# posidmux.net
KiCad netlist of a schematic drawn in EAGLE
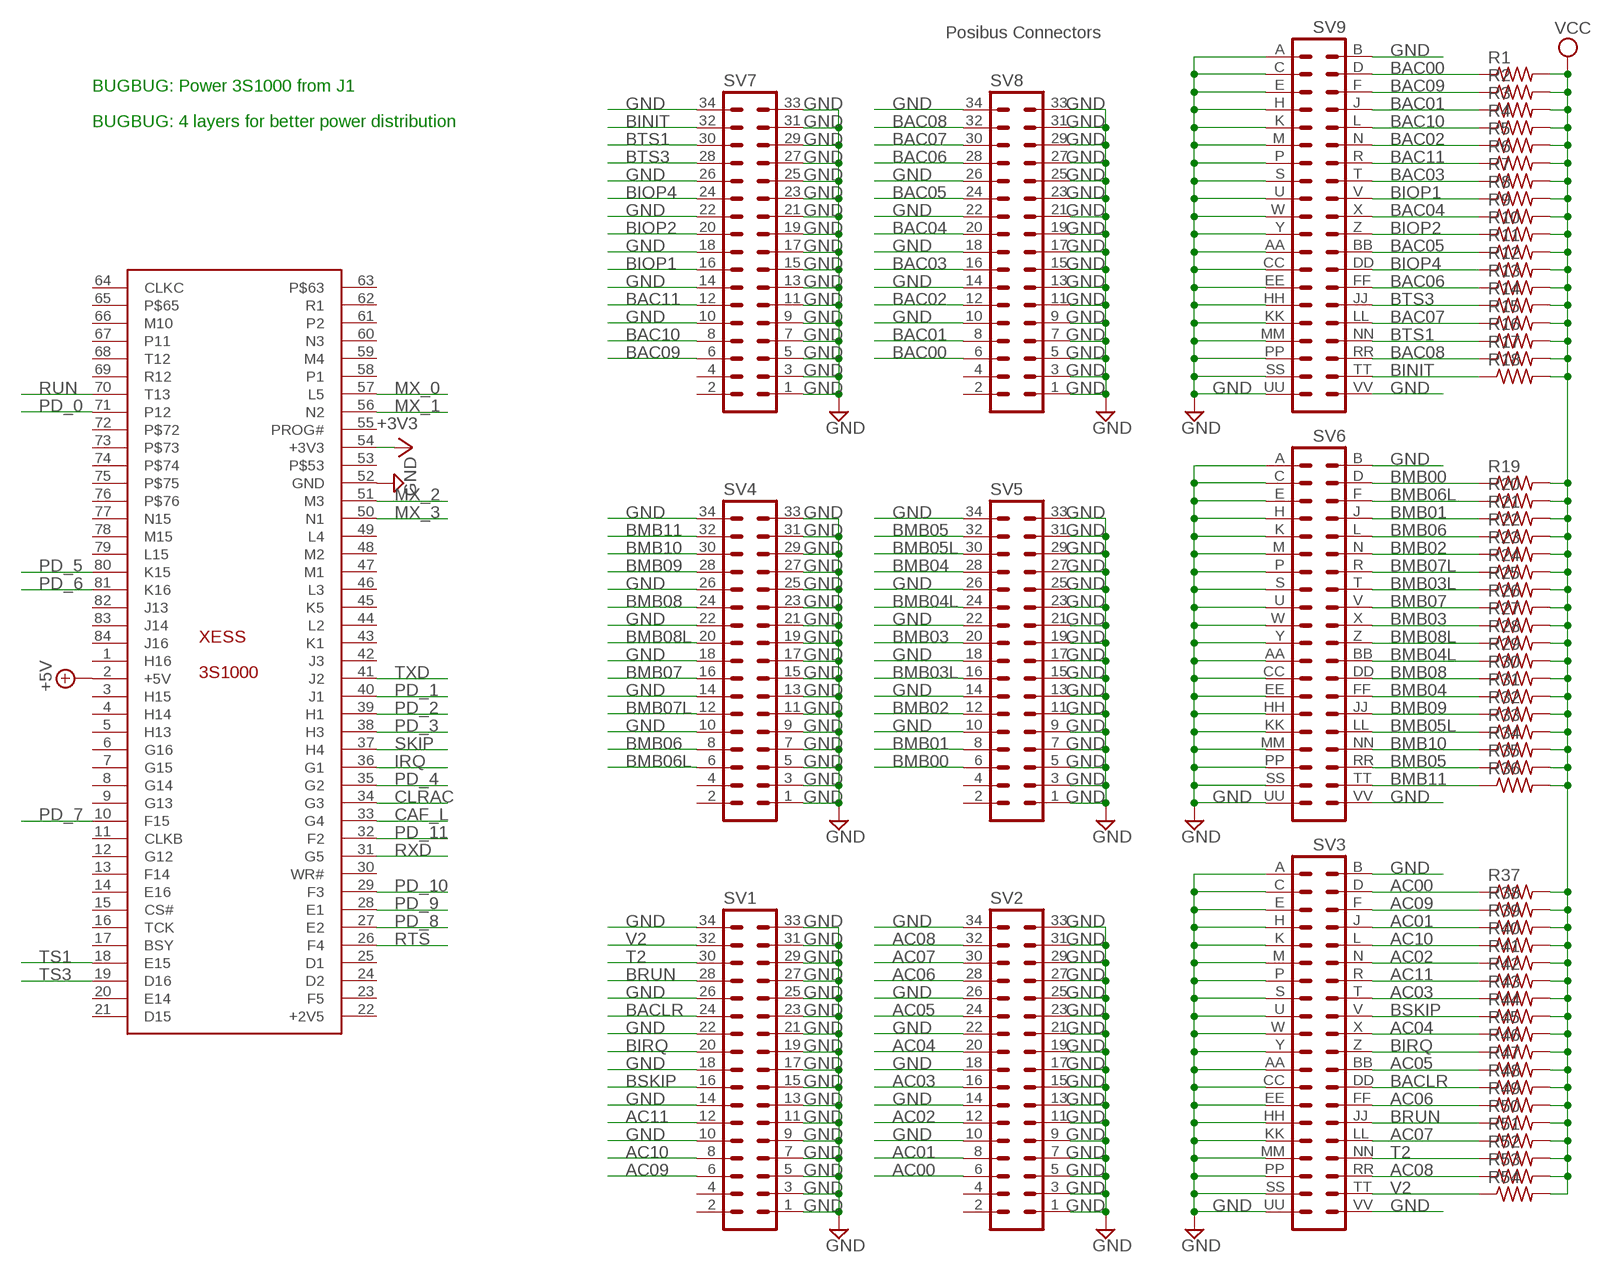
[diagram p0: schematic, sheet 1]
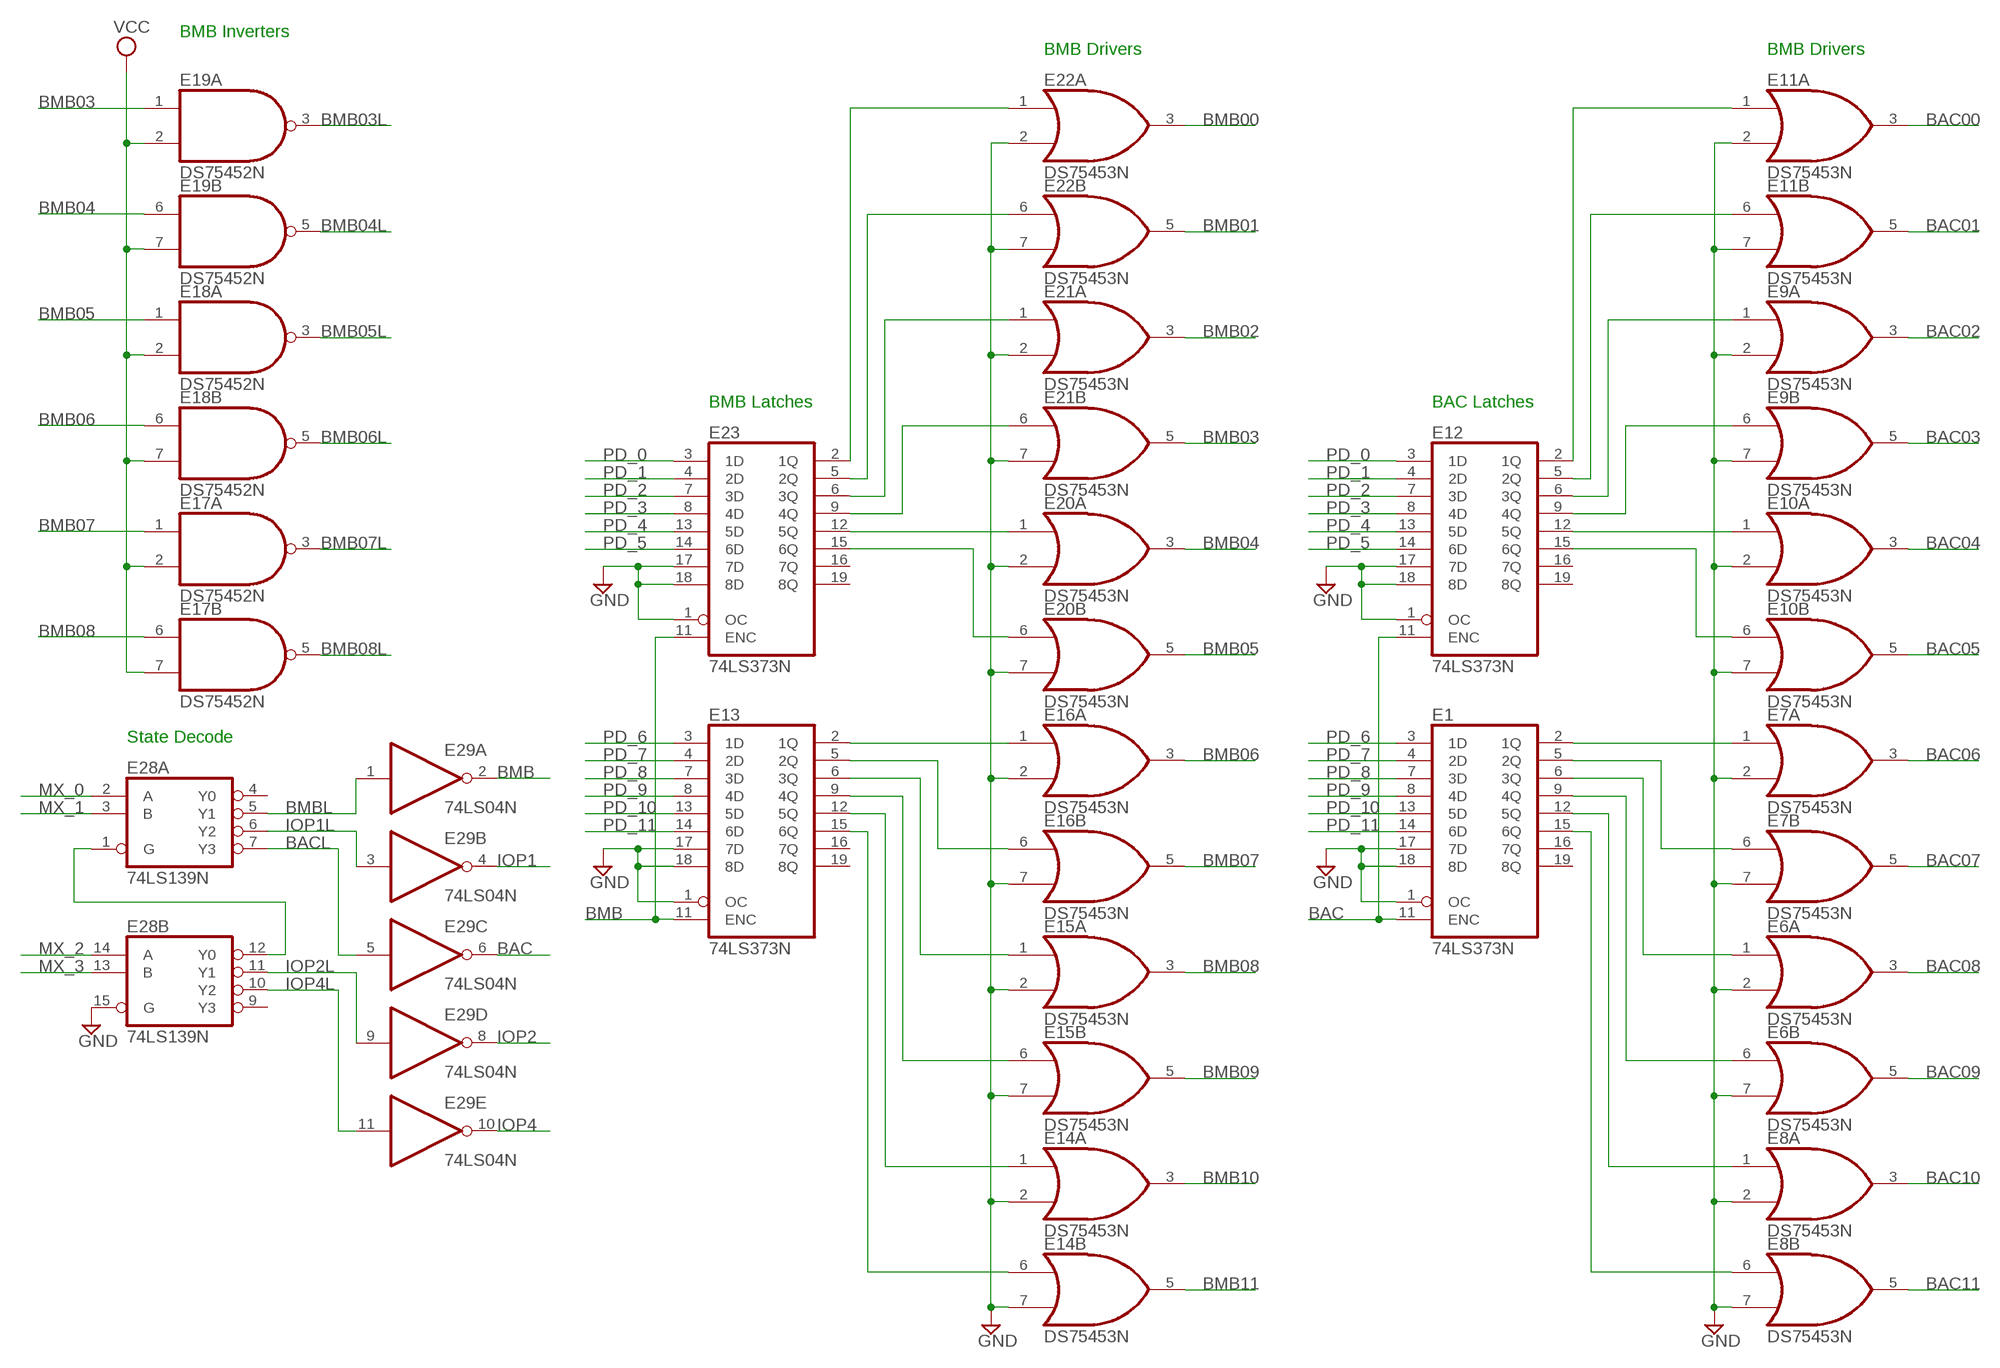
[diagram p1: schematic, sheet 2]
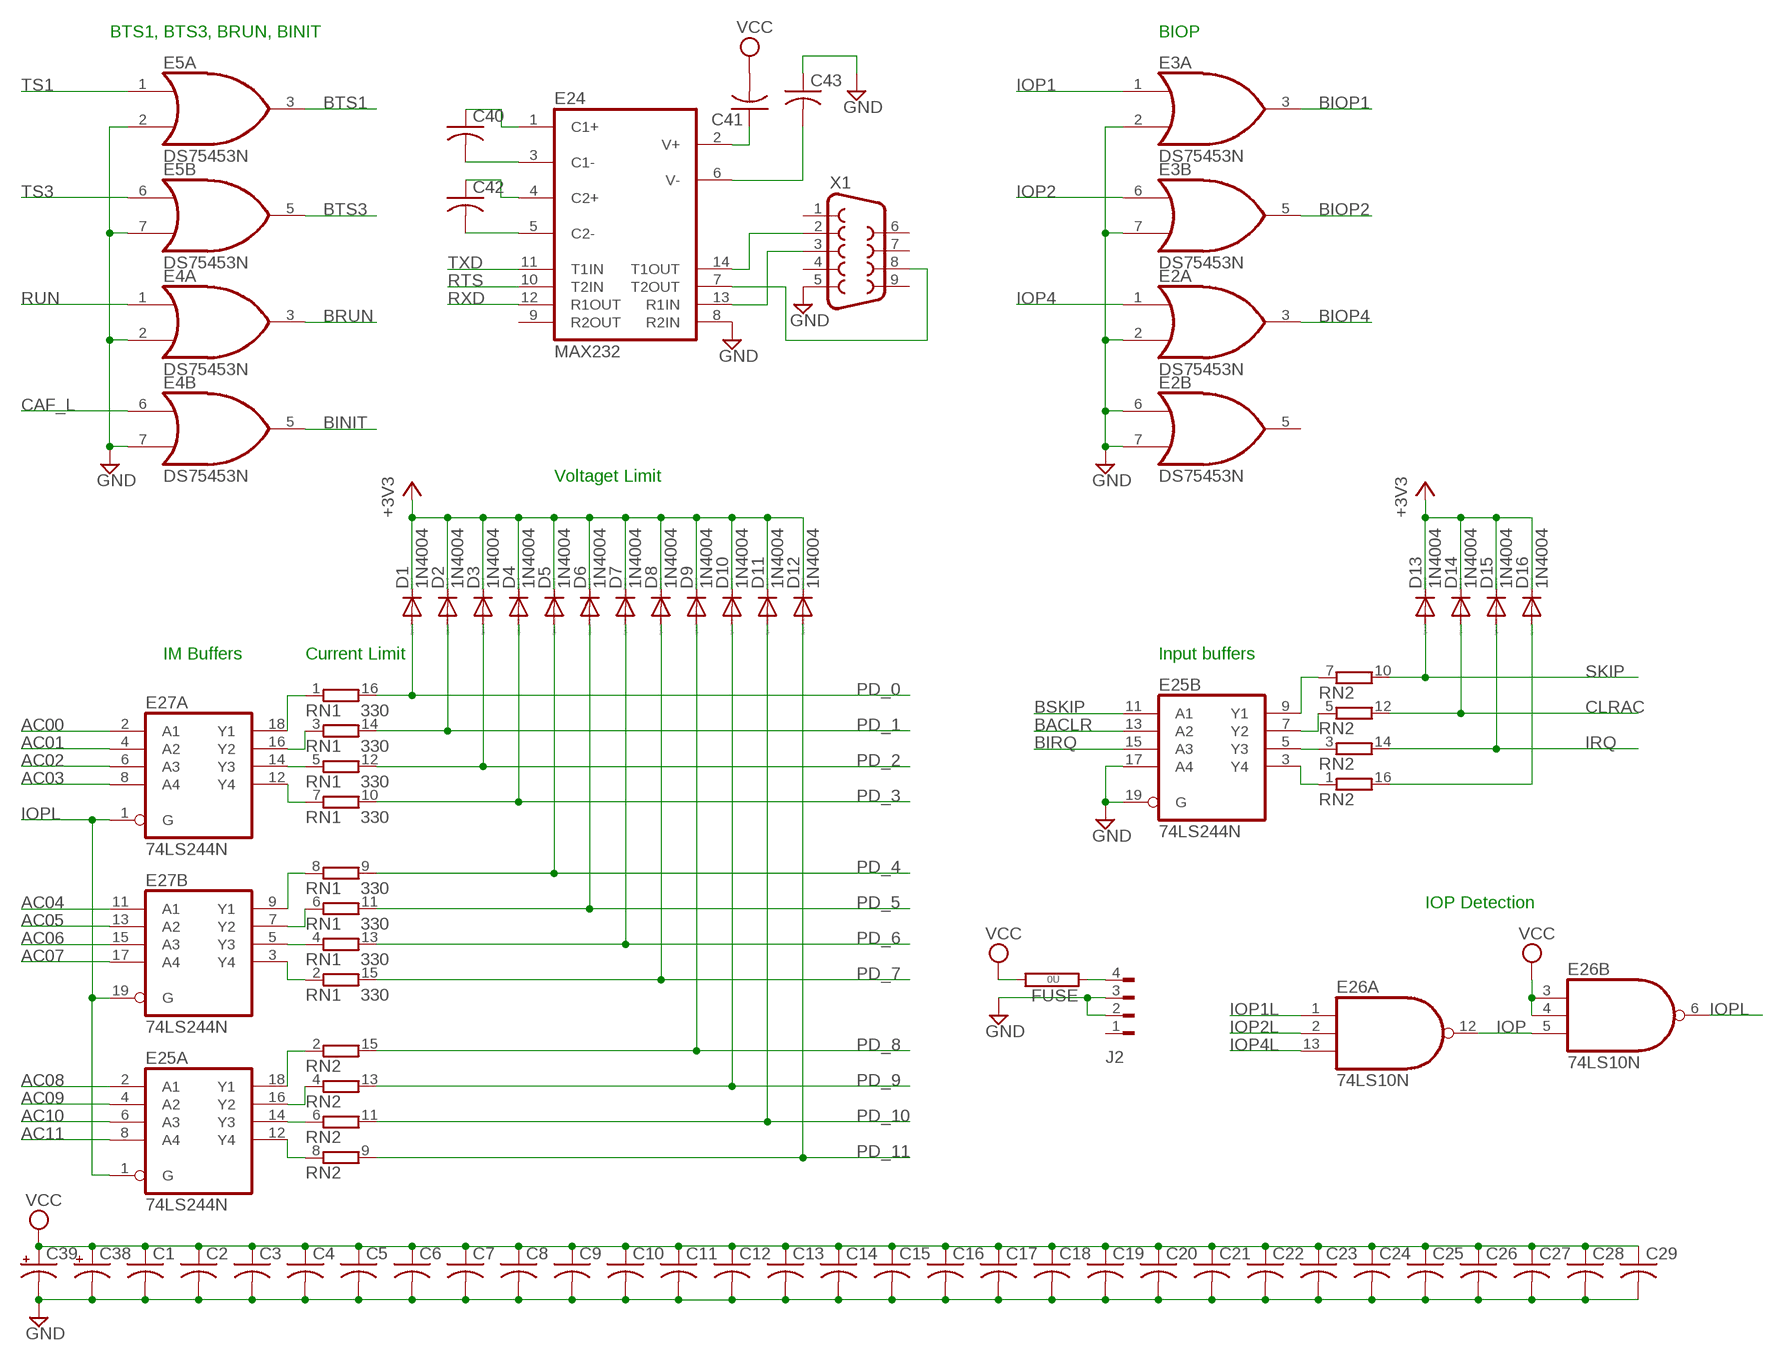
[diagram p2: schematic, sheet 3]

(export (version "E")
  (design (tool "Eeschema 10.0.6"))
  (components
    (comp (ref "E1")
      (value "74LS373N")
      (footprint "eagle-import:DIL20")
      (libsource (lib "eagle-import") (part "74373NLS"))
    )
    (comp (ref "E6")
      (value "DS75453N")
      (footprint "eagle-import:DIL08")
      (libsource (lib "eagle-import") (part "DS75453N"))
    )
    (comp (ref "E7")
      (value "DS75453N")
      (footprint "eagle-import:DIL08")
      (libsource (lib "eagle-import") (part "DS75453N"))
    )
    (comp (ref "E8")
      (value "DS75453N")
      (footprint "eagle-import:DIL08")
      (libsource (lib "eagle-import") (part "DS75453N"))
    )
    (comp (ref "E9")
      (value "DS75453N")
      (footprint "eagle-import:DIL08")
      (libsource (lib "eagle-import") (part "DS75453N"))
    )
    (comp (ref "E10")
      (value "DS75453N")
      (footprint "eagle-import:DIL08")
      (libsource (lib "eagle-import") (part "DS75453N"))
    )
    (comp (ref "E11")
      (value "DS75453N")
      (footprint "eagle-import:DIL08")
      (libsource (lib "eagle-import") (part "DS75453N"))
    )
    (comp (ref "E12")
      (value "74LS373N")
      (footprint "eagle-import:DIL20")
      (libsource (lib "eagle-import") (part "74373NLS"))
    )
    (comp (ref "E13")
      (value "74LS373N")
      (footprint "eagle-import:DIL20")
      (libsource (lib "eagle-import") (part "74373NLS"))
    )
    (comp (ref "E14")
      (value "DS75453N")
      (footprint "eagle-import:DIL08")
      (libsource (lib "eagle-import") (part "DS75453N"))
    )
    (comp (ref "E15")
      (value "DS75453N")
      (footprint "eagle-import:DIL08")
      (libsource (lib "eagle-import") (part "DS75453N"))
    )
    (comp (ref "E16")
      (value "DS75453N")
      (footprint "eagle-import:DIL08")
      (libsource (lib "eagle-import") (part "DS75453N"))
    )
    (comp (ref "E17")
      (value "DS75452N")
      (footprint "eagle-import:DIL08")
      (libsource (lib "eagle-import") (part "DS75452N"))
    )
    (comp (ref "E18")
      (value "DS75452N")
      (footprint "eagle-import:DIL08")
      (libsource (lib "eagle-import") (part "DS75452N"))
    )
    (comp (ref "E19")
      (value "DS75452N")
      (footprint "eagle-import:DIL08")
      (libsource (lib "eagle-import") (part "DS75452N"))
    )
    (comp (ref "E20")
      (value "DS75453N")
      (footprint "eagle-import:DIL08")
      (libsource (lib "eagle-import") (part "DS75453N"))
    )
    (comp (ref "E21")
      (value "DS75453N")
      (footprint "eagle-import:DIL08")
      (libsource (lib "eagle-import") (part "DS75453N"))
    )
    (comp (ref "E22")
      (value "DS75453N")
      (footprint "eagle-import:DIL08")
      (libsource (lib "eagle-import") (part "DS75453N"))
    )
    (comp (ref "E23")
      (value "74LS373N")
      (footprint "eagle-import:DIL20")
      (libsource (lib "eagle-import") (part "74373NLS"))
    )
    (comp (ref "E28")
      (value "74LS139N")
      (footprint "eagle-import:DIL16")
      (libsource (lib "eagle-import") (part "74139NLS"))
    )
    (comp (ref "E29")
      (value "74LS04N")
      (footprint "eagle-import:DIL14")
      (libsource (lib "eagle-import") (part "7404NLS"))
    )
    (comp (ref "C1")
      (value "C-US050-025X075")
      (footprint "eagle-import:C050-025X075")
      (libsource (lib "eagle-import") (part "C-US050-025X075"))
    )
    (comp (ref "C2")
      (value "C-US050-025X075")
      (footprint "eagle-import:C050-025X075")
      (libsource (lib "eagle-import") (part "C-US050-025X075"))
    )
    (comp (ref "C3")
      (value "C-US050-025X075")
      (footprint "eagle-import:C050-025X075")
      (libsource (lib "eagle-import") (part "C-US050-025X075"))
    )
    (comp (ref "C4")
      (value "C-US050-025X075")
      (footprint "eagle-import:C050-025X075")
      (libsource (lib "eagle-import") (part "C-US050-025X075"))
    )
    (comp (ref "C5")
      (value "C-US050-025X075")
      (footprint "eagle-import:C050-025X075")
      (libsource (lib "eagle-import") (part "C-US050-025X075"))
    )
    (comp (ref "C6")
      (value "C-US050-025X075")
      (footprint "eagle-import:C050-025X075")
      (libsource (lib "eagle-import") (part "C-US050-025X075"))
    )
    (comp (ref "C7")
      (value "C-US050-025X075")
      (footprint "eagle-import:C050-025X075")
      (libsource (lib "eagle-import") (part "C-US050-025X075"))
    )
    (comp (ref "C8")
      (value "C-US050-025X075")
      (footprint "eagle-import:C050-025X075")
      (libsource (lib "eagle-import") (part "C-US050-025X075"))
    )
    (comp (ref "C9")
      (value "C-US050-025X075")
      (footprint "eagle-import:C050-025X075")
      (libsource (lib "eagle-import") (part "C-US050-025X075"))
    )
    (comp (ref "C10")
      (value "C-US050-025X075")
      (footprint "eagle-import:C050-025X075")
      (libsource (lib "eagle-import") (part "C-US050-025X075"))
    )
    (comp (ref "C11")
      (value "C-US050-025X075")
      (footprint "eagle-import:C050-025X075")
      (libsource (lib "eagle-import") (part "C-US050-025X075"))
    )
    (comp (ref "C12")
      (value "C-US050-025X075")
      (footprint "eagle-import:C050-025X075")
      (libsource (lib "eagle-import") (part "C-US050-025X075"))
    )
    (comp (ref "C13")
      (value "C-US050-025X075")
      (footprint "eagle-import:C050-025X075")
      (libsource (lib "eagle-import") (part "C-US050-025X075"))
    )
    (comp (ref "C14")
      (value "C-US050-025X075")
      (footprint "eagle-import:C050-025X075")
      (libsource (lib "eagle-import") (part "C-US050-025X075"))
    )
    (comp (ref "C15")
      (value "C-US050-025X075")
      (footprint "eagle-import:C050-025X075")
      (libsource (lib "eagle-import") (part "C-US050-025X075"))
    )
    (comp (ref "C16")
      (value "C-US050-025X075")
      (footprint "eagle-import:C050-025X075")
      (libsource (lib "eagle-import") (part "C-US050-025X075"))
    )
    (comp (ref "C17")
      (value "C-US050-025X075")
      (footprint "eagle-import:C050-025X075")
      (libsource (lib "eagle-import") (part "C-US050-025X075"))
    )
    (comp (ref "C18")
      (value "C-US050-025X075")
      (footprint "eagle-import:C050-025X075")
      (libsource (lib "eagle-import") (part "C-US050-025X075"))
    )
    (comp (ref "C19")
      (value "C-US050-025X075")
      (footprint "eagle-import:C050-025X075")
      (libsource (lib "eagle-import") (part "C-US050-025X075"))
    )
    (comp (ref "C20")
      (value "C-US050-025X075")
      (footprint "eagle-import:C050-025X075")
      (libsource (lib "eagle-import") (part "C-US050-025X075"))
    )
    (comp (ref "C21")
      (value "C-US050-025X075")
      (footprint "eagle-import:C050-025X075")
      (libsource (lib "eagle-import") (part "C-US050-025X075"))
    )
    (comp (ref "C22")
      (value "C-US050-025X075")
      (footprint "eagle-import:C050-025X075")
      (libsource (lib "eagle-import") (part "C-US050-025X075"))
    )
    (comp (ref "C23")
      (value "C-US050-025X075")
      (footprint "eagle-import:C050-025X075")
      (libsource (lib "eagle-import") (part "C-US050-025X075"))
    )
    (comp (ref "C24")
      (value "C-US050-025X075")
      (footprint "eagle-import:C050-025X075")
      (libsource (lib "eagle-import") (part "C-US050-025X075"))
    )
    (comp (ref "C25")
      (value "C-US050-025X075")
      (footprint "eagle-import:C050-025X075")
      (libsource (lib "eagle-import") (part "C-US050-025X075"))
    )
    (comp (ref "C26")
      (value "C-US050-025X075")
      (footprint "eagle-import:C050-025X075")
      (libsource (lib "eagle-import") (part "C-US050-025X075"))
    )
    (comp (ref "C27")
      (value "C-US050-025X075")
      (footprint "eagle-import:C050-025X075")
      (libsource (lib "eagle-import") (part "C-US050-025X075"))
    )
    (comp (ref "C28")
      (value "C-US050-025X075")
      (footprint "eagle-import:C050-025X075")
      (libsource (lib "eagle-import") (part "C-US050-025X075"))
    )
    (comp (ref "C29")
      (value "C-US050-025X075")
      (footprint "eagle-import:C050-025X075")
      (libsource (lib "eagle-import") (part "C-US050-025X075"))
    )
    (comp (ref "C38")
      (value "CPOL-USE22-6AXIAL")
      (footprint "eagle-import:E22-6")
      (libsource (lib "eagle-import") (part "CPOL-USE22-6AXIAL"))
    )
    (comp (ref "C39")
      (value "CPOL-USE22-6AXIAL")
      (footprint "eagle-import:E22-6")
      (libsource (lib "eagle-import") (part "CPOL-USE22-6AXIAL"))
    )
    (comp (ref "C40")
      (value "C-US050-025X075")
      (footprint "eagle-import:C050-025X075")
      (libsource (lib "eagle-import") (part "C-US050-025X075"))
    )
    (comp (ref "C41")
      (value "C-US050-025X075")
      (footprint "eagle-import:C050-025X075")
      (libsource (lib "eagle-import") (part "C-US050-025X075"))
    )
    (comp (ref "C42")
      (value "C-US050-025X075")
      (footprint "eagle-import:C050-025X075")
      (libsource (lib "eagle-import") (part "C-US050-025X075"))
    )
    (comp (ref "C43")
      (value "C-US050-025X075")
      (footprint "eagle-import:C050-025X075")
      (libsource (lib "eagle-import") (part "C-US050-025X075"))
    )
    (comp (ref "D1")
      (value "1N4004")
      (footprint "eagle-import:DO41-10")
      (libsource (lib "eagle-import") (part "1N4004"))
    )
    (comp (ref "D2")
      (value "1N4004")
      (footprint "eagle-import:DO41-10")
      (libsource (lib "eagle-import") (part "1N4004"))
    )
    (comp (ref "D3")
      (value "1N4004")
      (footprint "eagle-import:DO41-10")
      (libsource (lib "eagle-import") (part "1N4004"))
    )
    (comp (ref "D4")
      (value "1N4004")
      (footprint "eagle-import:DO41-10")
      (libsource (lib "eagle-import") (part "1N4004"))
    )
    (comp (ref "D5")
      (value "1N4004")
      (footprint "eagle-import:DO41-10")
      (libsource (lib "eagle-import") (part "1N4004"))
    )
    (comp (ref "D6")
      (value "1N4004")
      (footprint "eagle-import:DO41-10")
      (libsource (lib "eagle-import") (part "1N4004"))
    )
    (comp (ref "D7")
      (value "1N4004")
      (footprint "eagle-import:DO41-10")
      (libsource (lib "eagle-import") (part "1N4004"))
    )
    (comp (ref "D8")
      (value "1N4004")
      (footprint "eagle-import:DO41-10")
      (libsource (lib "eagle-import") (part "1N4004"))
    )
    (comp (ref "D9")
      (value "1N4004")
      (footprint "eagle-import:DO41-10")
      (libsource (lib "eagle-import") (part "1N4004"))
    )
    (comp (ref "D10")
      (value "1N4004")
      (footprint "eagle-import:DO41-10")
      (libsource (lib "eagle-import") (part "1N4004"))
    )
    (comp (ref "D11")
      (value "1N4004")
      (footprint "eagle-import:DO41-10")
      (libsource (lib "eagle-import") (part "1N4004"))
    )
    (comp (ref "D12")
      (value "1N4004")
      (footprint "eagle-import:DO41-10")
      (libsource (lib "eagle-import") (part "1N4004"))
    )
    (comp (ref "D13")
      (value "1N4004")
      (footprint "eagle-import:DO41-10")
      (libsource (lib "eagle-import") (part "1N4004"))
    )
    (comp (ref "D14")
      (value "1N4004")
      (footprint "eagle-import:DO41-10")
      (libsource (lib "eagle-import") (part "1N4004"))
    )
    (comp (ref "D15")
      (value "1N4004")
      (footprint "eagle-import:DO41-10")
      (libsource (lib "eagle-import") (part "1N4004"))
    )
    (comp (ref "D16")
      (value "1N4004")
      (footprint "eagle-import:DO41-10")
      (libsource (lib "eagle-import") (part "1N4004"))
    )
    (comp (ref "E2")
      (value "DS75453N")
      (footprint "eagle-import:DIL08")
      (libsource (lib "eagle-import") (part "DS75453N"))
    )
    (comp (ref "E3")
      (value "DS75453N")
      (footprint "eagle-import:DIL08")
      (libsource (lib "eagle-import") (part "DS75453N"))
    )
    (comp (ref "E4")
      (value "DS75453N")
      (footprint "eagle-import:DIL08")
      (libsource (lib "eagle-import") (part "DS75453N"))
    )
    (comp (ref "E5")
      (value "DS75453N")
      (footprint "eagle-import:DIL08")
      (libsource (lib "eagle-import") (part "DS75453N"))
    )
    (comp (ref "E24")
      (value "MAX232")
      (footprint "eagle-import:DIL16")
      (fields (field (name "MF") "MAXIM") (field (name "MPN") "MAX232ACPE+"))
      (libsource (lib "eagle-import") (part "MAX232"))
    )
    (comp (ref "E25")
      (value "74LS244N")
      (footprint "eagle-import:DIL20")
      (libsource (lib "eagle-import") (part "74244NLS"))
    )
    (comp (ref "E26")
      (value "74LS10N")
      (footprint "eagle-import:DIL14")
      (libsource (lib "eagle-import") (part "7410NLS"))
    )
    (comp (ref "E27")
      (value "74LS244N")
      (footprint "eagle-import:DIL20")
      (libsource (lib "eagle-import") (part "74244NLS"))
    )
    (comp (ref "FUSE")
      (value "0R")
      (footprint "eagle-import:0R_10")
      (libsource (lib "eagle-import") (part "0R"))
    )
    (comp (ref "J2")
      (value "FLOPPY-4")
      (footprint "eagle-import:FLOPPY-4")
      (libsource (lib "eagle-import") (part "FLOPPY-4"))
    )
    (comp (ref "RN1")
      (value "330")
      (footprint "eagle-import:DIL16")
      (libsource (lib "eagle-import") (part "8R-P"))
    )
    (comp (ref "RN2")
      (value "8R-P")
      (footprint "eagle-import:DIL16")
      (libsource (lib "eagle-import") (part "8R-P"))
    )
    (comp (ref "X1")
      (value "F09HP")
      (footprint "eagle-import:F09HP")
      (libsource (lib "eagle-import") (part "F09HP"))
    )
    (comp (ref "R1")
      (value "R-US_0207/10")
      (footprint "eagle-import:0207_10")
      (libsource (lib "eagle-import") (part "R-US_0207/10"))
    )
    (comp (ref "R2")
      (value "R-US_0207/10")
      (footprint "eagle-import:0207_10")
      (libsource (lib "eagle-import") (part "R-US_0207/10"))
    )
    (comp (ref "R3")
      (value "R-US_0207/10")
      (footprint "eagle-import:0207_10")
      (libsource (lib "eagle-import") (part "R-US_0207/10"))
    )
    (comp (ref "R4")
      (value "R-US_0207/10")
      (footprint "eagle-import:0207_10")
      (libsource (lib "eagle-import") (part "R-US_0207/10"))
    )
    (comp (ref "R5")
      (value "R-US_0207/10")
      (footprint "eagle-import:0207_10")
      (libsource (lib "eagle-import") (part "R-US_0207/10"))
    )
    (comp (ref "R6")
      (value "R-US_0207/10")
      (footprint "eagle-import:0207_10")
      (libsource (lib "eagle-import") (part "R-US_0207/10"))
    )
    (comp (ref "R7")
      (value "R-US_0207/10")
      (footprint "eagle-import:0207_10")
      (libsource (lib "eagle-import") (part "R-US_0207/10"))
    )
    (comp (ref "R8")
      (value "R-US_0207/10")
      (footprint "eagle-import:0207_10")
      (libsource (lib "eagle-import") (part "R-US_0207/10"))
    )
    (comp (ref "R9")
      (value "R-US_0207/10")
      (footprint "eagle-import:0207_10")
      (libsource (lib "eagle-import") (part "R-US_0207/10"))
    )
    (comp (ref "R10")
      (value "R-US_0207/10")
      (footprint "eagle-import:0207_10")
      (libsource (lib "eagle-import") (part "R-US_0207/10"))
    )
    (comp (ref "R11")
      (value "R-US_0207/10")
      (footprint "eagle-import:0207_10")
      (libsource (lib "eagle-import") (part "R-US_0207/10"))
    )
    (comp (ref "R12")
      (value "R-US_0207/10")
      (footprint "eagle-import:0207_10")
      (libsource (lib "eagle-import") (part "R-US_0207/10"))
    )
    (comp (ref "R13")
      (value "R-US_0207/10")
      (footprint "eagle-import:0207_10")
      (libsource (lib "eagle-import") (part "R-US_0207/10"))
    )
    (comp (ref "R14")
      (value "R-US_0207/10")
      (footprint "eagle-import:0207_10")
      (libsource (lib "eagle-import") (part "R-US_0207/10"))
    )
    (comp (ref "R15")
      (value "R-US_0207/10")
      (footprint "eagle-import:0207_10")
      (libsource (lib "eagle-import") (part "R-US_0207/10"))
    )
    (comp (ref "R16")
      (value "R-US_0207/10")
      (footprint "eagle-import:0207_10")
      (libsource (lib "eagle-import") (part "R-US_0207/10"))
    )
    (comp (ref "R17")
      (value "R-US_0207/10")
      (footprint "eagle-import:0207_10")
      (libsource (lib "eagle-import") (part "R-US_0207/10"))
    )
    (comp (ref "R18")
      (value "R-US_0207/10")
      (footprint "eagle-import:0207_10")
      (libsource (lib "eagle-import") (part "R-US_0207/10"))
    )
    (comp (ref "R19")
      (value "R-US_0207/10")
      (footprint "eagle-import:0207_10")
      (libsource (lib "eagle-import") (part "R-US_0207/10"))
    )
    (comp (ref "R20")
      (value "R-US_0207/10")
      (footprint "eagle-import:0207_10")
      (libsource (lib "eagle-import") (part "R-US_0207/10"))
    )
    (comp (ref "R21")
      (value "R-US_0207/10")
      (footprint "eagle-import:0207_10")
      (libsource (lib "eagle-import") (part "R-US_0207/10"))
    )
    (comp (ref "R22")
      (value "R-US_0207/10")
      (footprint "eagle-import:0207_10")
      (libsource (lib "eagle-import") (part "R-US_0207/10"))
    )
    (comp (ref "R23")
      (value "R-US_0207/10")
      (footprint "eagle-import:0207_10")
      (libsource (lib "eagle-import") (part "R-US_0207/10"))
    )
    (comp (ref "R24")
      (value "R-US_0207/10")
      (footprint "eagle-import:0207_10")
      (libsource (lib "eagle-import") (part "R-US_0207/10"))
    )
    (comp (ref "R25")
      (value "R-US_0207/10")
      (footprint "eagle-import:0207_10")
      (libsource (lib "eagle-import") (part "R-US_0207/10"))
    )
    (comp (ref "R26")
      (value "R-US_0207/10")
      (footprint "eagle-import:0207_10")
      (libsource (lib "eagle-import") (part "R-US_0207/10"))
    )
    (comp (ref "R27")
      (value "R-US_0207/10")
      (footprint "eagle-import:0207_10")
      (libsource (lib "eagle-import") (part "R-US_0207/10"))
    )
    (comp (ref "R28")
      (value "R-US_0207/10")
      (footprint "eagle-import:0207_10")
      (libsource (lib "eagle-import") (part "R-US_0207/10"))
    )
    (comp (ref "R29")
      (value "R-US_0207/10")
      (footprint "eagle-import:0207_10")
      (libsource (lib "eagle-import") (part "R-US_0207/10"))
    )
    (comp (ref "R30")
      (value "R-US_0207/10")
      (footprint "eagle-import:0207_10")
      (libsource (lib "eagle-import") (part "R-US_0207/10"))
    )
    (comp (ref "R31")
      (value "R-US_0207/10")
      (footprint "eagle-import:0207_10")
      (libsource (lib "eagle-import") (part "R-US_0207/10"))
    )
    (comp (ref "R32")
      (value "R-US_0207/10")
      (footprint "eagle-import:0207_10")
      (libsource (lib "eagle-import") (part "R-US_0207/10"))
    )
    (comp (ref "R33")
      (value "R-US_0207/10")
      (footprint "eagle-import:0207_10")
      (libsource (lib "eagle-import") (part "R-US_0207/10"))
    )
    (comp (ref "R34")
      (value "R-US_0207/10")
      (footprint "eagle-import:0207_10")
      (libsource (lib "eagle-import") (part "R-US_0207/10"))
    )
    (comp (ref "R35")
      (value "R-US_0207/10")
      (footprint "eagle-import:0207_10")
      (libsource (lib "eagle-import") (part "R-US_0207/10"))
    )
    (comp (ref "R36")
      (value "R-US_0207/10")
      (footprint "eagle-import:0207_10")
      (libsource (lib "eagle-import") (part "R-US_0207/10"))
    )
    (comp (ref "R37")
      (value "R-US_0207/10")
      (footprint "eagle-import:0207_10")
      (libsource (lib "eagle-import") (part "R-US_0207/10"))
    )
    (comp (ref "R38")
      (value "R-US_0207/10")
      (footprint "eagle-import:0207_10")
      (libsource (lib "eagle-import") (part "R-US_0207/10"))
    )
    (comp (ref "R39")
      (value "R-US_0207/10")
      (footprint "eagle-import:0207_10")
      (libsource (lib "eagle-import") (part "R-US_0207/10"))
    )
    (comp (ref "R40")
      (value "R-US_0207/10")
      (footprint "eagle-import:0207_10")
      (libsource (lib "eagle-import") (part "R-US_0207/10"))
    )
    (comp (ref "R41")
      (value "R-US_0207/10")
      (footprint "eagle-import:0207_10")
      (libsource (lib "eagle-import") (part "R-US_0207/10"))
    )
    (comp (ref "R42")
      (value "R-US_0207/10")
      (footprint "eagle-import:0207_10")
      (libsource (lib "eagle-import") (part "R-US_0207/10"))
    )
    (comp (ref "R43")
      (value "R-US_0207/10")
      (footprint "eagle-import:0207_10")
      (libsource (lib "eagle-import") (part "R-US_0207/10"))
    )
    (comp (ref "R44")
      (value "R-US_0207/10")
      (footprint "eagle-import:0207_10")
      (libsource (lib "eagle-import") (part "R-US_0207/10"))
    )
    (comp (ref "R45")
      (value "R-US_0207/10")
      (footprint "eagle-import:0207_10")
      (libsource (lib "eagle-import") (part "R-US_0207/10"))
    )
    (comp (ref "R46")
      (value "R-US_0207/10")
      (footprint "eagle-import:0207_10")
      (libsource (lib "eagle-import") (part "R-US_0207/10"))
    )
    (comp (ref "R47")
      (value "R-US_0207/10")
      (footprint "eagle-import:0207_10")
      (libsource (lib "eagle-import") (part "R-US_0207/10"))
    )
    (comp (ref "R48")
      (value "R-US_0207/10")
      (footprint "eagle-import:0207_10")
      (libsource (lib "eagle-import") (part "R-US_0207/10"))
    )
    (comp (ref "R49")
      (value "R-US_0207/10")
      (footprint "eagle-import:0207_10")
      (libsource (lib "eagle-import") (part "R-US_0207/10"))
    )
    (comp (ref "R50")
      (value "R-US_0207/10")
      (footprint "eagle-import:0207_10")
      (libsource (lib "eagle-import") (part "R-US_0207/10"))
    )
    (comp (ref "R51")
      (value "R-US_0207/10")
      (footprint "eagle-import:0207_10")
      (libsource (lib "eagle-import") (part "R-US_0207/10"))
    )
    (comp (ref "R52")
      (value "R-US_0207/10")
      (footprint "eagle-import:0207_10")
      (libsource (lib "eagle-import") (part "R-US_0207/10"))
    )
    (comp (ref "R53")
      (value "R-US_0207/10")
      (footprint "eagle-import:0207_10")
      (libsource (lib "eagle-import") (part "R-US_0207/10"))
    )
    (comp (ref "R54")
      (value "R-US_0207/10")
      (footprint "eagle-import:0207_10")
      (libsource (lib "eagle-import") (part "R-US_0207/10"))
    )
    (comp (ref "SV1")
      (value "MA17-2")
      (footprint "eagle-import:MA17-2")
      (libsource (lib "eagle-import") (part "MA17-2"))
    )
    (comp (ref "SV2")
      (value "MA17-2")
      (footprint "eagle-import:MA17-2")
      (libsource (lib "eagle-import") (part "MA17-2"))
    )
    (comp (ref "SV3")
      (value "DEC40PINV")
      (footprint "eagle-import:DEC40PINV")
      (libsource (lib "eagle-import") (part "DEC40PINV"))
    )
    (comp (ref "SV4")
      (value "MA17-2")
      (footprint "eagle-import:MA17-2")
      (libsource (lib "eagle-import") (part "MA17-2"))
    )
    (comp (ref "SV5")
      (value "MA17-2")
      (footprint "eagle-import:MA17-2")
      (libsource (lib "eagle-import") (part "MA17-2"))
    )
    (comp (ref "SV6")
      (value "DEC40PINV")
      (footprint "eagle-import:DEC40PINV")
      (libsource (lib "eagle-import") (part "DEC40PINV"))
    )
    (comp (ref "SV7")
      (value "MA17-2")
      (footprint "eagle-import:MA17-2")
      (libsource (lib "eagle-import") (part "MA17-2"))
    )
    (comp (ref "SV8")
      (value "MA17-2")
      (footprint "eagle-import:MA17-2")
      (libsource (lib "eagle-import") (part "MA17-2"))
    )
    (comp (ref "SV9")
      (value "DEC40PINV")
      (footprint "eagle-import:DEC40PINV")
      (libsource (lib "eagle-import") (part "DEC40PINV"))
    )
    (comp (ref "XESS")
      (value "3S1000")
      (footprint "eagle-import:3S1000")
      (libsource (lib "eagle-import") (part "3S1000"))
    )
  )
  (nets
    (net (code "1") (name "+2V5") (class "Default")
      (node (ref "XESS") (pin "22") (pinfunction "+2V5_22") (pintype "power_in"))
    )
    (net (code "2") (name "+3V3") (class "Default")
      (node (ref "D1") (pin "C") (pinfunction "C_C") (pintype "passive"))
      (node (ref "D10") (pin "C") (pinfunction "C_C") (pintype "passive"))
      (node (ref "D11") (pin "C") (pinfunction "C_C") (pintype "passive"))
      (node (ref "D12") (pin "C") (pinfunction "C_C") (pintype "passive"))
      (node (ref "D13") (pin "C") (pinfunction "C_C") (pintype "passive"))
      (node (ref "D14") (pin "C") (pinfunction "C_C") (pintype "passive"))
      (node (ref "D15") (pin "C") (pinfunction "C_C") (pintype "passive"))
      (node (ref "D16") (pin "C") (pinfunction "C_C") (pintype "passive"))
      (node (ref "D2") (pin "C") (pinfunction "C_C") (pintype "passive"))
      (node (ref "D3") (pin "C") (pinfunction "C_C") (pintype "passive"))
      (node (ref "D4") (pin "C") (pinfunction "C_C") (pintype "passive"))
      (node (ref "D5") (pin "C") (pinfunction "C_C") (pintype "passive"))
      (node (ref "D6") (pin "C") (pinfunction "C_C") (pintype "passive"))
      (node (ref "D7") (pin "C") (pinfunction "C_C") (pintype "passive"))
      (node (ref "D8") (pin "C") (pinfunction "C_C") (pintype "passive"))
      (node (ref "D9") (pin "C") (pinfunction "C_C") (pintype "passive"))
      (node (ref "XESS") (pin "54") (pinfunction "+3V3_54") (pintype "power_in"))
    )
    (net (code "3") (name "+5V") (class "Default")
      (node (ref "XESS") (pin "2") (pinfunction "+5V_2") (pintype "power_in"))
    )
    (net (code "4") (name "AC00") (class "Default")
      (node (ref "E27") (pin "2") (pinfunction "A1_2") (pintype "input"))
      (node (ref "R37") (pin "1") (pinfunction "1_1") (pintype "passive"))
      (node (ref "SV2") (pin "6") (pinfunction "6_6") (pintype "passive"))
      (node (ref "SV3") (pin "D") (pinfunction "4_D") (pintype "bidirectional"))
    )
    (net (code "5") (name "AC01") (class "Default")
      (node (ref "E27") (pin "4") (pinfunction "A2_4") (pintype "input"))
      (node (ref "R39") (pin "1") (pinfunction "1_1") (pintype "passive"))
      (node (ref "SV2") (pin "8") (pinfunction "8_8") (pintype "passive"))
      (node (ref "SV3") (pin "J") (pinfunction "8_J") (pintype "bidirectional"))
    )
    (net (code "6") (name "AC02") (class "Default")
      (node (ref "E27") (pin "6") (pinfunction "A3_6") (pintype "input"))
      (node (ref "R41") (pin "1") (pinfunction "1_1") (pintype "passive"))
      (node (ref "SV2") (pin "12") (pinfunction "12_12") (pintype "passive"))
      (node (ref "SV3") (pin "N") (pinfunction "12_N") (pintype "bidirectional"))
    )
    (net (code "7") (name "AC03") (class "Default")
      (node (ref "E27") (pin "8") (pinfunction "A4_8") (pintype "input"))
      (node (ref "R43") (pin "1") (pinfunction "1_1") (pintype "passive"))
      (node (ref "SV2") (pin "16") (pinfunction "16_16") (pintype "passive"))
      (node (ref "SV3") (pin "T") (pinfunction "16_T") (pintype "bidirectional"))
    )
    (net (code "8") (name "AC04") (class "Default")
      (node (ref "E27") (pin "11") (pinfunction "A1_11") (pintype "input"))
      (node (ref "R45") (pin "1") (pinfunction "1_1") (pintype "passive"))
      (node (ref "SV2") (pin "20") (pinfunction "20_20") (pintype "passive"))
      (node (ref "SV3") (pin "X") (pinfunction "20_X") (pintype "bidirectional"))
    )
    (net (code "9") (name "AC05") (class "Default")
      (node (ref "E27") (pin "13") (pinfunction "A2_13") (pintype "input"))
      (node (ref "R47") (pin "1") (pinfunction "1_1") (pintype "passive"))
      (node (ref "SV2") (pin "24") (pinfunction "24_24") (pintype "passive"))
      (node (ref "SV3") (pin "BB") (pinfunction "24_BB") (pintype "bidirectional"))
    )
    (net (code "10") (name "AC06") (class "Default")
      (node (ref "E27") (pin "15") (pinfunction "A3_15") (pintype "input"))
      (node (ref "R49") (pin "1") (pinfunction "1_1") (pintype "passive"))
      (node (ref "SV2") (pin "28") (pinfunction "28_28") (pintype "passive"))
      (node (ref "SV3") (pin "FF") (pinfunction "28_FF") (pintype "bidirectional"))
    )
    (net (code "11") (name "AC07") (class "Default")
      (node (ref "E27") (pin "17") (pinfunction "A4_17") (pintype "input"))
      (node (ref "R51") (pin "1") (pinfunction "1_1") (pintype "passive"))
      (node (ref "SV2") (pin "30") (pinfunction "30_30") (pintype "passive"))
      (node (ref "SV3") (pin "LL") (pinfunction "32_LL") (pintype "bidirectional"))
    )
    (net (code "12") (name "AC08") (class "Default")
      (node (ref "E25") (pin "2") (pinfunction "A1_2") (pintype "input"))
      (node (ref "R53") (pin "1") (pinfunction "1_1") (pintype "passive"))
      (node (ref "SV2") (pin "32") (pinfunction "32_32") (pintype "passive"))
      (node (ref "SV3") (pin "RR") (pinfunction "36_RR") (pintype "bidirectional"))
    )
    (net (code "13") (name "AC09") (class "Default")
      (node (ref "E25") (pin "4") (pinfunction "A2_4") (pintype "input"))
      (node (ref "R38") (pin "1") (pinfunction "1_1") (pintype "passive"))
      (node (ref "SV1") (pin "6") (pinfunction "6_6") (pintype "passive"))
      (node (ref "SV3") (pin "F") (pinfunction "6_F") (pintype "bidirectional"))
    )
    (net (code "14") (name "AC10") (class "Default")
      (node (ref "E25") (pin "6") (pinfunction "A3_6") (pintype "input"))
      (node (ref "R40") (pin "1") (pinfunction "1_1") (pintype "passive"))
      (node (ref "SV1") (pin "8") (pinfunction "8_8") (pintype "passive"))
      (node (ref "SV3") (pin "L") (pinfunction "10_L") (pintype "bidirectional"))
    )
    (net (code "15") (name "AC11") (class "Default")
      (node (ref "E25") (pin "8") (pinfunction "A4_8") (pintype "input"))
      (node (ref "R42") (pin "1") (pinfunction "1_1") (pintype "passive"))
      (node (ref "SV1") (pin "12") (pinfunction "12_12") (pintype "passive"))
      (node (ref "SV3") (pin "R") (pinfunction "14_R") (pintype "bidirectional"))
    )
    (net (code "16") (name "BAC") (class "Default")
      (node (ref "E1") (pin "11") (pinfunction "ENC_11") (pintype "input"))
      (node (ref "E12") (pin "11") (pinfunction "ENC_11") (pintype "input"))
      (node (ref "E29") (pin "6") (pinfunction "O_6") (pintype "output"))
    )
    (net (code "17") (name "BAC00") (class "Default")
      (node (ref "E11") (pin "3") (pinfunction "O_3") (pintype "open_collector"))
      (node (ref "R1") (pin "1") (pinfunction "1_1") (pintype "passive"))
      (node (ref "SV8") (pin "6") (pinfunction "6_6") (pintype "passive"))
      (node (ref "SV9") (pin "D") (pinfunction "4_D") (pintype "bidirectional"))
    )
    (net (code "18") (name "BAC01") (class "Default")
      (node (ref "E11") (pin "5") (pinfunction "O_5") (pintype "open_collector"))
      (node (ref "R3") (pin "1") (pinfunction "1_1") (pintype "passive"))
      (node (ref "SV8") (pin "8") (pinfunction "8_8") (pintype "passive"))
      (node (ref "SV9") (pin "J") (pinfunction "8_J") (pintype "bidirectional"))
    )
    (net (code "19") (name "BAC02") (class "Default")
      (node (ref "E9") (pin "3") (pinfunction "O_3") (pintype "open_collector"))
      (node (ref "R5") (pin "1") (pinfunction "1_1") (pintype "passive"))
      (node (ref "SV8") (pin "12") (pinfunction "12_12") (pintype "passive"))
      (node (ref "SV9") (pin "N") (pinfunction "12_N") (pintype "bidirectional"))
    )
    (net (code "20") (name "BAC03") (class "Default")
      (node (ref "E9") (pin "5") (pinfunction "O_5") (pintype "open_collector"))
      (node (ref "R7") (pin "1") (pinfunction "1_1") (pintype "passive"))
      (node (ref "SV8") (pin "16") (pinfunction "16_16") (pintype "passive"))
      (node (ref "SV9") (pin "T") (pinfunction "16_T") (pintype "bidirectional"))
    )
    (net (code "21") (name "BAC04") (class "Default")
      (node (ref "E10") (pin "3") (pinfunction "O_3") (pintype "open_collector"))
      (node (ref "R9") (pin "1") (pinfunction "1_1") (pintype "passive"))
      (node (ref "SV8") (pin "20") (pinfunction "20_20") (pintype "passive"))
      (node (ref "SV9") (pin "X") (pinfunction "20_X") (pintype "bidirectional"))
    )
    (net (code "22") (name "BAC05") (class "Default")
      (node (ref "E10") (pin "5") (pinfunction "O_5") (pintype "open_collector"))
      (node (ref "R11") (pin "1") (pinfunction "1_1") (pintype "passive"))
      (node (ref "SV8") (pin "24") (pinfunction "24_24") (pintype "passive"))
      (node (ref "SV9") (pin "BB") (pinfunction "24_BB") (pintype "bidirectional"))
    )
    (net (code "23") (name "BAC06") (class "Default")
      (node (ref "E7") (pin "3") (pinfunction "O_3") (pintype "open_collector"))
      (node (ref "R13") (pin "1") (pinfunction "1_1") (pintype "passive"))
      (node (ref "SV8") (pin "28") (pinfunction "28_28") (pintype "passive"))
      (node (ref "SV9") (pin "FF") (pinfunction "28_FF") (pintype "bidirectional"))
    )
    (net (code "24") (name "BAC07") (class "Default")
      (node (ref "E7") (pin "5") (pinfunction "O_5") (pintype "open_collector"))
      (node (ref "R15") (pin "1") (pinfunction "1_1") (pintype "passive"))
      (node (ref "SV8") (pin "30") (pinfunction "30_30") (pintype "passive"))
      (node (ref "SV9") (pin "LL") (pinfunction "32_LL") (pintype "bidirectional"))
    )
    (net (code "25") (name "BAC08") (class "Default")
      (node (ref "E6") (pin "3") (pinfunction "O_3") (pintype "open_collector"))
      (node (ref "R17") (pin "1") (pinfunction "1_1") (pintype "passive"))
      (node (ref "SV8") (pin "32") (pinfunction "32_32") (pintype "passive"))
      (node (ref "SV9") (pin "RR") (pinfunction "36_RR") (pintype "bidirectional"))
    )
    (net (code "26") (name "BAC09") (class "Default")
      (node (ref "E6") (pin "5") (pinfunction "O_5") (pintype "open_collector"))
      (node (ref "R2") (pin "1") (pinfunction "1_1") (pintype "passive"))
      (node (ref "SV7") (pin "6") (pinfunction "6_6") (pintype "passive"))
      (node (ref "SV9") (pin "F") (pinfunction "6_F") (pintype "bidirectional"))
    )
    (net (code "27") (name "BAC10") (class "Default")
      (node (ref "E8") (pin "3") (pinfunction "O_3") (pintype "open_collector"))
      (node (ref "R4") (pin "1") (pinfunction "1_1") (pintype "passive"))
      (node (ref "SV7") (pin "8") (pinfunction "8_8") (pintype "passive"))
      (node (ref "SV9") (pin "L") (pinfunction "10_L") (pintype "bidirectional"))
    )
    (net (code "28") (name "BAC11") (class "Default")
      (node (ref "E8") (pin "5") (pinfunction "O_5") (pintype "open_collector"))
      (node (ref "R6") (pin "1") (pinfunction "1_1") (pintype "passive"))
      (node (ref "SV7") (pin "12") (pinfunction "12_12") (pintype "passive"))
      (node (ref "SV9") (pin "R") (pinfunction "14_R") (pintype "bidirectional"))
    )
    (net (code "29") (name "BACL") (class "Default")
      (node (ref "E28") (pin "7") (pinfunction "Y3_7") (pintype "output"))
      (node (ref "E29") (pin "5") (pinfunction "I_5") (pintype "input"))
    )
    (net (code "30") (name "BACLR") (class "Default")
      (node (ref "E25") (pin "13") (pinfunction "A2_13") (pintype "input"))
      (node (ref "R48") (pin "1") (pinfunction "1_1") (pintype "passive"))
      (node (ref "SV1") (pin "24") (pinfunction "24_24") (pintype "passive"))
      (node (ref "SV3") (pin "DD") (pinfunction "26_DD") (pintype "bidirectional"))
    )
    (net (code "31") (name "BINIT") (class "Default")
      (node (ref "E4") (pin "5") (pinfunction "O_5") (pintype "open_collector"))
      (node (ref "R18") (pin "1") (pinfunction "1_1") (pintype "passive"))
      (node (ref "SV7") (pin "32") (pinfunction "32_32") (pintype "passive"))
      (node (ref "SV9") (pin "TT") (pinfunction "38_TT") (pintype "bidirectional"))
    )
    (net (code "32") (name "BIOP1") (class "Default")
      (node (ref "E3") (pin "3") (pinfunction "O_3") (pintype "open_collector"))
      (node (ref "R8") (pin "1") (pinfunction "1_1") (pintype "passive"))
      (node (ref "SV7") (pin "16") (pinfunction "16_16") (pintype "passive"))
      (node (ref "SV9") (pin "V") (pinfunction "18_V") (pintype "bidirectional"))
    )
    (net (code "33") (name "BIOP2") (class "Default")
      (node (ref "E3") (pin "5") (pinfunction "O_5") (pintype "open_collector"))
      (node (ref "R10") (pin "1") (pinfunction "1_1") (pintype "passive"))
      (node (ref "SV7") (pin "20") (pinfunction "20_20") (pintype "passive"))
      (node (ref "SV9") (pin "Z") (pinfunction "22_Z") (pintype "bidirectional"))
    )
    (net (code "34") (name "BIOP4") (class "Default")
      (node (ref "E2") (pin "3") (pinfunction "O_3") (pintype "open_collector"))
      (node (ref "R12") (pin "1") (pinfunction "1_1") (pintype "passive"))
      (node (ref "SV7") (pin "24") (pinfunction "24_24") (pintype "passive"))
      (node (ref "SV9") (pin "DD") (pinfunction "26_DD") (pintype "bidirectional"))
    )
    (net (code "35") (name "BIRQ") (class "Default")
      (node (ref "E25") (pin "15") (pinfunction "A3_15") (pintype "input"))
      (node (ref "R46") (pin "1") (pinfunction "1_1") (pintype "passive"))
      (node (ref "SV1") (pin "20") (pinfunction "20_20") (pintype "passive"))
      (node (ref "SV3") (pin "Z") (pinfunction "22_Z") (pintype "bidirectional"))
    )
    (net (code "36") (name "BMB") (class "Default")
      (node (ref "E13") (pin "11") (pinfunction "ENC_11") (pintype "input"))
      (node (ref "E23") (pin "11") (pinfunction "ENC_11") (pintype "input"))
      (node (ref "E29") (pin "2") (pinfunction "O_2") (pintype "output"))
    )
    (net (code "37") (name "BMB00") (class "Default")
      (node (ref "E22") (pin "3") (pinfunction "O_3") (pintype "open_collector"))
      (node (ref "R19") (pin "1") (pinfunction "1_1") (pintype "passive"))
      (node (ref "SV5") (pin "6") (pinfunction "6_6") (pintype "passive"))
      (node (ref "SV6") (pin "D") (pinfunction "4_D") (pintype "bidirectional"))
    )
    (net (code "38") (name "BMB01") (class "Default")
      (node (ref "E22") (pin "5") (pinfunction "O_5") (pintype "open_collector"))
      (node (ref "R21") (pin "1") (pinfunction "1_1") (pintype "passive"))
      (node (ref "SV5") (pin "8") (pinfunction "8_8") (pintype "passive"))
      (node (ref "SV6") (pin "J") (pinfunction "8_J") (pintype "bidirectional"))
    )
    (net (code "39") (name "BMB02") (class "Default")
      (node (ref "E21") (pin "3") (pinfunction "O_3") (pintype "open_collector"))
      (node (ref "R23") (pin "1") (pinfunction "1_1") (pintype "passive"))
      (node (ref "SV5") (pin "12") (pinfunction "12_12") (pintype "passive"))
      (node (ref "SV6") (pin "N") (pinfunction "12_N") (pintype "bidirectional"))
    )
    (net (code "40") (name "BMB03") (class "Default")
      (node (ref "E19") (pin "1") (pinfunction "I0_1") (pintype "input"))
      (node (ref "E21") (pin "5") (pinfunction "O_5") (pintype "open_collector"))
      (node (ref "R27") (pin "1") (pinfunction "1_1") (pintype "passive"))
      (node (ref "SV5") (pin "20") (pinfunction "20_20") (pintype "passive"))
      (node (ref "SV6") (pin "X") (pinfunction "20_X") (pintype "bidirectional"))
    )
    (net (code "41") (name "BMB03L") (class "Default")
      (node (ref "E19") (pin "3") (pinfunction "O_3") (pintype "open_collector"))
      (node (ref "R25") (pin "1") (pinfunction "1_1") (pintype "passive"))
      (node (ref "SV5") (pin "16") (pinfunction "16_16") (pintype "passive"))
      (node (ref "SV6") (pin "T") (pinfunction "16_T") (pintype "bidirectional"))
    )
    (net (code "42") (name "BMB04") (class "Default")
      (node (ref "E19") (pin "6") (pinfunction "I0_6") (pintype "input"))
      (node (ref "E20") (pin "3") (pinfunction "O_3") (pintype "open_collector"))
      (node (ref "R31") (pin "1") (pinfunction "1_1") (pintype "passive"))
      (node (ref "SV5") (pin "28") (pinfunction "28_28") (pintype "passive"))
      (node (ref "SV6") (pin "FF") (pinfunction "28_FF") (pintype "bidirectional"))
    )
    (net (code "43") (name "BMB04L") (class "Default")
      (node (ref "E19") (pin "5") (pinfunction "O_5") (pintype "open_collector"))
      (node (ref "R29") (pin "1") (pinfunction "1_1") (pintype "passive"))
      (node (ref "SV5") (pin "24") (pinfunction "24_24") (pintype "passive"))
      (node (ref "SV6") (pin "BB") (pinfunction "24_BB") (pintype "bidirectional"))
    )
    (net (code "44") (name "BMB05") (class "Default")
      (node (ref "E18") (pin "1") (pinfunction "I0_1") (pintype "input"))
      (node (ref "E20") (pin "5") (pinfunction "O_5") (pintype "open_collector"))
      (node (ref "R35") (pin "1") (pinfunction "1_1") (pintype "passive"))
      (node (ref "SV5") (pin "32") (pinfunction "32_32") (pintype "passive"))
      (node (ref "SV6") (pin "RR") (pinfunction "36_RR") (pintype "bidirectional"))
    )
    (net (code "45") (name "BMB05L") (class "Default")
      (node (ref "E18") (pin "3") (pinfunction "O_3") (pintype "open_collector"))
      (node (ref "R33") (pin "1") (pinfunction "1_1") (pintype "passive"))
      (node (ref "SV5") (pin "30") (pinfunction "30_30") (pintype "passive"))
      (node (ref "SV6") (pin "LL") (pinfunction "32_LL") (pintype "bidirectional"))
    )
    (net (code "46") (name "BMB06") (class "Default")
      (node (ref "E16") (pin "3") (pinfunction "O_3") (pintype "open_collector"))
      (node (ref "E18") (pin "6") (pinfunction "I0_6") (pintype "input"))
      (node (ref "R22") (pin "1") (pinfunction "1_1") (pintype "passive"))
      (node (ref "SV4") (pin "8") (pinfunction "8_8") (pintype "passive"))
      (node (ref "SV6") (pin "L") (pinfunction "10_L") (pintype "bidirectional"))
    )
    (net (code "47") (name "BMB06L") (class "Default")
      (node (ref "E18") (pin "5") (pinfunction "O_5") (pintype "open_collector"))
      (node (ref "R20") (pin "1") (pinfunction "1_1") (pintype "passive"))
      (node (ref "SV4") (pin "6") (pinfunction "6_6") (pintype "passive"))
      (node (ref "SV6") (pin "F") (pinfunction "6_F") (pintype "bidirectional"))
    )
    (net (code "48") (name "BMB07") (class "Default")
      (node (ref "E16") (pin "5") (pinfunction "O_5") (pintype "open_collector"))
      (node (ref "E17") (pin "1") (pinfunction "I0_1") (pintype "input"))
      (node (ref "R26") (pin "1") (pinfunction "1_1") (pintype "passive"))
      (node (ref "SV4") (pin "16") (pinfunction "16_16") (pintype "passive"))
      (node (ref "SV6") (pin "V") (pinfunction "18_V") (pintype "bidirectional"))
    )
    (net (code "49") (name "BMB07L") (class "Default")
      (node (ref "E17") (pin "3") (pinfunction "O_3") (pintype "open_collector"))
      (node (ref "R24") (pin "1") (pinfunction "1_1") (pintype "passive"))
      (node (ref "SV4") (pin "12") (pinfunction "12_12") (pintype "passive"))
      (node (ref "SV6") (pin "R") (pinfunction "14_R") (pintype "bidirectional"))
    )
    (net (code "50") (name "BMB08") (class "Default")
      (node (ref "E15") (pin "3") (pinfunction "O_3") (pintype "open_collector"))
      (node (ref "E17") (pin "6") (pinfunction "I0_6") (pintype "input"))
      (node (ref "R30") (pin "1") (pinfunction "1_1") (pintype "passive"))
      (node (ref "SV4") (pin "24") (pinfunction "24_24") (pintype "passive"))
      (node (ref "SV6") (pin "DD") (pinfunction "26_DD") (pintype "bidirectional"))
    )
    (net (code "51") (name "BMB08L") (class "Default")
      (node (ref "E17") (pin "5") (pinfunction "O_5") (pintype "open_collector"))
      (node (ref "R28") (pin "1") (pinfunction "1_1") (pintype "passive"))
      (node (ref "SV4") (pin "20") (pinfunction "20_20") (pintype "passive"))
      (node (ref "SV6") (pin "Z") (pinfunction "22_Z") (pintype "bidirectional"))
    )
    (net (code "52") (name "BMB09") (class "Default")
      (node (ref "E15") (pin "5") (pinfunction "O_5") (pintype "open_collector"))
      (node (ref "R32") (pin "1") (pinfunction "1_1") (pintype "passive"))
      (node (ref "SV4") (pin "28") (pinfunction "28_28") (pintype "passive"))
      (node (ref "SV6") (pin "JJ") (pinfunction "30_JJ") (pintype "bidirectional"))
    )
    (net (code "53") (name "BMB10") (class "Default")
      (node (ref "E14") (pin "3") (pinfunction "O_3") (pintype "open_collector"))
      (node (ref "R34") (pin "1") (pinfunction "1_1") (pintype "passive"))
      (node (ref "SV4") (pin "30") (pinfunction "30_30") (pintype "passive"))
      (node (ref "SV6") (pin "NN") (pinfunction "34_NN") (pintype "bidirectional"))
    )
    (net (code "54") (name "BMB11") (class "Default")
      (node (ref "E14") (pin "5") (pinfunction "O_5") (pintype "open_collector"))
      (node (ref "R36") (pin "1") (pinfunction "1_1") (pintype "passive"))
      (node (ref "SV4") (pin "32") (pinfunction "32_32") (pintype "passive"))
      (node (ref "SV6") (pin "TT") (pinfunction "38_TT") (pintype "bidirectional"))
    )
    (net (code "55") (name "BMBL") (class "Default")
      (node (ref "E28") (pin "5") (pinfunction "Y1_5") (pintype "output"))
      (node (ref "E29") (pin "1") (pinfunction "I_1") (pintype "input"))
    )
    (net (code "56") (name "BRUN") (class "Default")
      (node (ref "E4") (pin "3") (pinfunction "O_3") (pintype "open_collector"))
      (node (ref "R50") (pin "1") (pinfunction "1_1") (pintype "passive"))
      (node (ref "SV1") (pin "28") (pinfunction "28_28") (pintype "passive"))
      (node (ref "SV3") (pin "JJ") (pinfunction "30_JJ") (pintype "bidirectional"))
    )
    (net (code "57") (name "BSKIP") (class "Default")
      (node (ref "E25") (pin "11") (pinfunction "A1_11") (pintype "input"))
      (node (ref "R44") (pin "1") (pinfunction "1_1") (pintype "passive"))
      (node (ref "SV1") (pin "16") (pinfunction "16_16") (pintype "passive"))
      (node (ref "SV3") (pin "V") (pinfunction "18_V") (pintype "bidirectional"))
    )
    (net (code "58") (name "BTS1") (class "Default")
      (node (ref "E5") (pin "3") (pinfunction "O_3") (pintype "open_collector"))
      (node (ref "R16") (pin "1") (pinfunction "1_1") (pintype "passive"))
      (node (ref "SV7") (pin "30") (pinfunction "30_30") (pintype "passive"))
      (node (ref "SV9") (pin "NN") (pinfunction "34_NN") (pintype "bidirectional"))
    )
    (net (code "59") (name "BTS3") (class "Default")
      (node (ref "E5") (pin "5") (pinfunction "O_5") (pintype "open_collector"))
      (node (ref "R14") (pin "1") (pinfunction "1_1") (pintype "passive"))
      (node (ref "SV7") (pin "28") (pinfunction "28_28") (pintype "passive"))
      (node (ref "SV9") (pin "JJ") (pinfunction "30_JJ") (pintype "bidirectional"))
    )
    (net (code "60") (name "CAF_L") (class "Default")
      (node (ref "E4") (pin "6") (pinfunction "I0_6") (pintype "input"))
      (node (ref "XESS") (pin "33") (pinfunction "G4_33") (pintype "bidirectional"))
    )
    (net (code "61") (name "CLRAC") (class "Default")
      (node (ref "D14") (pin "A") (pinfunction "A_A") (pintype "passive"))
      (node (ref "RN2") (pin "12") (pinfunction "2_12") (pintype "passive"))
      (node (ref "XESS") (pin "34") (pinfunction "G3_34") (pintype "bidirectional"))
    )
    (net (code "62") (name "GND") (class "Default")
      (node (ref "C1") (pin "2") (pinfunction "2_2") (pintype "passive"))
      (node (ref "C10") (pin "2") (pinfunction "2_2") (pintype "passive"))
      (node (ref "C11") (pin "2") (pinfunction "2_2") (pintype "passive"))
      (node (ref "C12") (pin "2") (pinfunction "2_2") (pintype "passive"))
      (node (ref "C13") (pin "2") (pinfunction "2_2") (pintype "passive"))
      (node (ref "C14") (pin "2") (pinfunction "2_2") (pintype "passive"))
      (node (ref "C15") (pin "2") (pinfunction "2_2") (pintype "passive"))
      (node (ref "C16") (pin "2") (pinfunction "2_2") (pintype "passive"))
      (node (ref "C17") (pin "2") (pinfunction "2_2") (pintype "passive"))
      (node (ref "C18") (pin "2") (pinfunction "2_2") (pintype "passive"))
      (node (ref "C19") (pin "2") (pinfunction "2_2") (pintype "passive"))
      (node (ref "C2") (pin "2") (pinfunction "2_2") (pintype "passive"))
      (node (ref "C20") (pin "2") (pinfunction "2_2") (pintype "passive"))
      (node (ref "C21") (pin "2") (pinfunction "2_2") (pintype "passive"))
      (node (ref "C22") (pin "2") (pinfunction "2_2") (pintype "passive"))
      (node (ref "C23") (pin "2") (pinfunction "2_2") (pintype "passive"))
      (node (ref "C24") (pin "2") (pinfunction "2_2") (pintype "passive"))
      (node (ref "C25") (pin "2") (pinfunction "2_2") (pintype "passive"))
      (node (ref "C26") (pin "2") (pinfunction "2_2") (pintype "passive"))
      (node (ref "C27") (pin "2") (pinfunction "2_2") (pintype "passive"))
      (node (ref "C28") (pin "2") (pinfunction "2_2") (pintype "passive"))
      (node (ref "C29") (pin "2") (pinfunction "2_2") (pintype "passive"))
      (node (ref "C3") (pin "2") (pinfunction "2_2") (pintype "passive"))
      (node (ref "C38") (pin "-") (pinfunction "-_-") (pintype "passive"))
      (node (ref "C39") (pin "-") (pinfunction "-_-") (pintype "passive"))
      (node (ref "C4") (pin "2") (pinfunction "2_2") (pintype "passive"))
      (node (ref "C43") (pin "1") (pinfunction "1_1") (pintype "passive"))
      (node (ref "C5") (pin "2") (pinfunction "2_2") (pintype "passive"))
      (node (ref "C6") (pin "2") (pinfunction "2_2") (pintype "passive"))
      (node (ref "C7") (pin "2") (pinfunction "2_2") (pintype "passive"))
      (node (ref "C8") (pin "2") (pinfunction "2_2") (pintype "passive"))
      (node (ref "C9") (pin "2") (pinfunction "2_2") (pintype "passive"))
      (node (ref "E1") (pin "1") (pinfunction "OC_1") (pintype "input"))
      (node (ref "E1") (pin "17") (pinfunction "7D_17") (pintype "input"))
      (node (ref "E1") (pin "18") (pinfunction "8D_18") (pintype "input"))
      (node (ref "E10") (pin "2") (pinfunction "I1_2") (pintype "input"))
      (node (ref "E10") (pin "7") (pinfunction "I1_7") (pintype "input"))
      (node (ref "E11") (pin "2") (pinfunction "I1_2") (pintype "input"))
      (node (ref "E11") (pin "7") (pinfunction "I1_7") (pintype "input"))
      (node (ref "E12") (pin "1") (pinfunction "OC_1") (pintype "input"))
      (node (ref "E12") (pin "17") (pinfunction "7D_17") (pintype "input"))
      (node (ref "E12") (pin "18") (pinfunction "8D_18") (pintype "input"))
      (node (ref "E13") (pin "1") (pinfunction "OC_1") (pintype "input"))
      (node (ref "E13") (pin "17") (pinfunction "7D_17") (pintype "input"))
      (node (ref "E13") (pin "18") (pinfunction "8D_18") (pintype "input"))
      (node (ref "E14") (pin "2") (pinfunction "I1_2") (pintype "input"))
      (node (ref "E14") (pin "7") (pinfunction "I1_7") (pintype "input"))
      (node (ref "E15") (pin "2") (pinfunction "I1_2") (pintype "input"))
      (node (ref "E15") (pin "7") (pinfunction "I1_7") (pintype "input"))
      (node (ref "E16") (pin "2") (pinfunction "I1_2") (pintype "input"))
      (node (ref "E16") (pin "7") (pinfunction "I1_7") (pintype "input"))
      (node (ref "E2") (pin "2") (pinfunction "I1_2") (pintype "input"))
      (node (ref "E2") (pin "6") (pinfunction "I0_6") (pintype "input"))
      (node (ref "E2") (pin "7") (pinfunction "I1_7") (pintype "input"))
      (node (ref "E20") (pin "2") (pinfunction "I1_2") (pintype "input"))
      (node (ref "E20") (pin "7") (pinfunction "I1_7") (pintype "input"))
      (node (ref "E21") (pin "2") (pinfunction "I1_2") (pintype "input"))
      (node (ref "E21") (pin "7") (pinfunction "I1_7") (pintype "input"))
      (node (ref "E22") (pin "2") (pinfunction "I1_2") (pintype "input"))
      (node (ref "E22") (pin "7") (pinfunction "I1_7") (pintype "input"))
      (node (ref "E23") (pin "1") (pinfunction "OC_1") (pintype "input"))
      (node (ref "E23") (pin "17") (pinfunction "7D_17") (pintype "input"))
      (node (ref "E23") (pin "18") (pinfunction "8D_18") (pintype "input"))
      (node (ref "E24") (pin "8") (pinfunction "R2IN_8") (pintype "input"))
      (node (ref "E25") (pin "17") (pinfunction "A4_17") (pintype "input"))
      (node (ref "E25") (pin "19") (pinfunction "G_19") (pintype "input"))
      (node (ref "E28") (pin "15") (pinfunction "G_15") (pintype "input"))
      (node (ref "E3") (pin "2") (pinfunction "I1_2") (pintype "input"))
      (node (ref "E3") (pin "7") (pinfunction "I1_7") (pintype "input"))
      (node (ref "E4") (pin "2") (pinfunction "I1_2") (pintype "input"))
      (node (ref "E4") (pin "7") (pinfunction "I1_7") (pintype "input"))
      (node (ref "E5") (pin "2") (pinfunction "I1_2") (pintype "input"))
      (node (ref "E5") (pin "7") (pinfunction "I1_7") (pintype "input"))
      (node (ref "E6") (pin "2") (pinfunction "I1_2") (pintype "input"))
      (node (ref "E6") (pin "7") (pinfunction "I1_7") (pintype "input"))
      (node (ref "E7") (pin "2") (pinfunction "I1_2") (pintype "input"))
      (node (ref "E7") (pin "7") (pinfunction "I1_7") (pintype "input"))
      (node (ref "E8") (pin "2") (pinfunction "I1_2") (pintype "input"))
      (node (ref "E8") (pin "7") (pinfunction "I1_7") (pintype "input"))
      (node (ref "E9") (pin "2") (pinfunction "I1_2") (pintype "input"))
      (node (ref "E9") (pin "7") (pinfunction "I1_7") (pintype "input"))
      (node (ref "J2") (pin "2") (pinfunction "2_2") (pintype "passive"))
      (node (ref "J2") (pin "3") (pinfunction "3_3") (pintype "passive"))
      (node (ref "SV1") (pin "1") (pinfunction "1_1") (pintype "passive"))
      (node (ref "SV1") (pin "10") (pinfunction "10_10") (pintype "passive"))
      (node (ref "SV1") (pin "11") (pinfunction "11_11") (pintype "passive"))
      (node (ref "SV1") (pin "13") (pinfunction "13_13") (pintype "passive"))
      (node (ref "SV1") (pin "14") (pinfunction "14_14") (pintype "passive"))
      (node (ref "SV1") (pin "15") (pinfunction "15_15") (pintype "passive"))
      (node (ref "SV1") (pin "17") (pinfunction "17_17") (pintype "passive"))
      (node (ref "SV1") (pin "18") (pinfunction "18_18") (pintype "passive"))
      (node (ref "SV1") (pin "19") (pinfunction "19_19") (pintype "passive"))
      (node (ref "SV1") (pin "21") (pinfunction "21_21") (pintype "passive"))
      (node (ref "SV1") (pin "22") (pinfunction "22_22") (pintype "passive"))
      (node (ref "SV1") (pin "23") (pinfunction "23_23") (pintype "passive"))
      (node (ref "SV1") (pin "25") (pinfunction "25_25") (pintype "passive"))
      (node (ref "SV1") (pin "26") (pinfunction "26_26") (pintype "passive"))
      (node (ref "SV1") (pin "27") (pinfunction "27_27") (pintype "passive"))
      (node (ref "SV1") (pin "29") (pinfunction "29_29") (pintype "passive"))
      (node (ref "SV1") (pin "3") (pinfunction "3_3") (pintype "passive"))
      (node (ref "SV1") (pin "31") (pinfunction "31_31") (pintype "passive"))
      (node (ref "SV1") (pin "33") (pinfunction "33_33") (pintype "passive"))
      (node (ref "SV1") (pin "34") (pinfunction "34_34") (pintype "passive"))
      (node (ref "SV1") (pin "5") (pinfunction "5_5") (pintype "passive"))
      (node (ref "SV1") (pin "7") (pinfunction "7_7") (pintype "passive"))
      (node (ref "SV1") (pin "9") (pinfunction "9_9") (pintype "passive"))
      (node (ref "SV2") (pin "1") (pinfunction "1_1") (pintype "passive"))
      (node (ref "SV2") (pin "10") (pinfunction "10_10") (pintype "passive"))
      (node (ref "SV2") (pin "11") (pinfunction "11_11") (pintype "passive"))
      (node (ref "SV2") (pin "13") (pinfunction "13_13") (pintype "passive"))
      (node (ref "SV2") (pin "14") (pinfunction "14_14") (pintype "passive"))
      (node (ref "SV2") (pin "15") (pinfunction "15_15") (pintype "passive"))
      (node (ref "SV2") (pin "17") (pinfunction "17_17") (pintype "passive"))
      (node (ref "SV2") (pin "18") (pinfunction "18_18") (pintype "passive"))
      (node (ref "SV2") (pin "19") (pinfunction "19_19") (pintype "passive"))
      (node (ref "SV2") (pin "21") (pinfunction "21_21") (pintype "passive"))
      (node (ref "SV2") (pin "22") (pinfunction "22_22") (pintype "passive"))
      (node (ref "SV2") (pin "23") (pinfunction "23_23") (pintype "passive"))
      (node (ref "SV2") (pin "25") (pinfunction "25_25") (pintype "passive"))
      (node (ref "SV2") (pin "26") (pinfunction "26_26") (pintype "passive"))
      (node (ref "SV2") (pin "27") (pinfunction "27_27") (pintype "passive"))
      (node (ref "SV2") (pin "29") (pinfunction "29_29") (pintype "passive"))
      (node (ref "SV2") (pin "3") (pinfunction "3_3") (pintype "passive"))
      (node (ref "SV2") (pin "31") (pinfunction "31_31") (pintype "passive"))
      (node (ref "SV2") (pin "33") (pinfunction "33_33") (pintype "passive"))
      (node (ref "SV2") (pin "34") (pinfunction "34_34") (pintype "passive"))
      (node (ref "SV2") (pin "5") (pinfunction "5_5") (pintype "passive"))
      (node (ref "SV2") (pin "7") (pinfunction "7_7") (pintype "passive"))
      (node (ref "SV2") (pin "9") (pinfunction "9_9") (pintype "passive"))
      (node (ref "SV3") (pin "A") (pinfunction "1_A") (pintype "bidirectional"))
      (node (ref "SV3") (pin "AA") (pinfunction "23_AA") (pintype "bidirectional"))
      (node (ref "SV3") (pin "B") (pinfunction "2_B") (pintype "bidirectional"))
      (node (ref "SV3") (pin "C") (pinfunction "3_C") (pintype "bidirectional"))
      (node (ref "SV3") (pin "CC") (pinfunction "25_CC") (pintype "bidirectional"))
      (node (ref "SV3") (pin "E") (pinfunction "5_E") (pintype "bidirectional"))
      (node (ref "SV3") (pin "EE") (pinfunction "27_EE") (pintype "bidirectional"))
      (node (ref "SV3") (pin "H") (pinfunction "7_H") (pintype "bidirectional"))
      (node (ref "SV3") (pin "HH") (pinfunction "29_HH") (pintype "bidirectional"))
      (node (ref "SV3") (pin "K") (pinfunction "9_K") (pintype "bidirectional"))
      (node (ref "SV3") (pin "KK") (pinfunction "31_KK") (pintype "bidirectional"))
      (node (ref "SV3") (pin "M") (pinfunction "11_M") (pintype "bidirectional"))
      (node (ref "SV3") (pin "MM") (pinfunction "33_MM") (pintype "bidirectional"))
      (node (ref "SV3") (pin "P") (pinfunction "13_P") (pintype "bidirectional"))
      (node (ref "SV3") (pin "PP") (pinfunction "35_PP") (pintype "bidirectional"))
      (node (ref "SV3") (pin "S") (pinfunction "15_S") (pintype "bidirectional"))
      (node (ref "SV3") (pin "SS") (pinfunction "37_SS") (pintype "bidirectional"))
      (node (ref "SV3") (pin "U") (pinfunction "17_U") (pintype "bidirectional"))
      (node (ref "SV3") (pin "UU") (pinfunction "39_UU") (pintype "bidirectional"))
      (node (ref "SV3") (pin "VV") (pinfunction "40_VV") (pintype "bidirectional"))
      (node (ref "SV3") (pin "W") (pinfunction "19_W") (pintype "bidirectional"))
      (node (ref "SV3") (pin "Y") (pinfunction "21_Y") (pintype "bidirectional"))
      (node (ref "SV4") (pin "1") (pinfunction "1_1") (pintype "passive"))
      (node (ref "SV4") (pin "10") (pinfunction "10_10") (pintype "passive"))
      (node (ref "SV4") (pin "11") (pinfunction "11_11") (pintype "passive"))
      (node (ref "SV4") (pin "13") (pinfunction "13_13") (pintype "passive"))
      (node (ref "SV4") (pin "14") (pinfunction "14_14") (pintype "passive"))
      (node (ref "SV4") (pin "15") (pinfunction "15_15") (pintype "passive"))
      (node (ref "SV4") (pin "17") (pinfunction "17_17") (pintype "passive"))
      (node (ref "SV4") (pin "18") (pinfunction "18_18") (pintype "passive"))
      (node (ref "SV4") (pin "19") (pinfunction "19_19") (pintype "passive"))
      (node (ref "SV4") (pin "21") (pinfunction "21_21") (pintype "passive"))
      (node (ref "SV4") (pin "22") (pinfunction "22_22") (pintype "passive"))
      (node (ref "SV4") (pin "23") (pinfunction "23_23") (pintype "passive"))
      (node (ref "SV4") (pin "25") (pinfunction "25_25") (pintype "passive"))
      (node (ref "SV4") (pin "26") (pinfunction "26_26") (pintype "passive"))
      (node (ref "SV4") (pin "27") (pinfunction "27_27") (pintype "passive"))
      (node (ref "SV4") (pin "29") (pinfunction "29_29") (pintype "passive"))
      (node (ref "SV4") (pin "3") (pinfunction "3_3") (pintype "passive"))
      (node (ref "SV4") (pin "31") (pinfunction "31_31") (pintype "passive"))
      (node (ref "SV4") (pin "33") (pinfunction "33_33") (pintype "passive"))
      (node (ref "SV4") (pin "34") (pinfunction "34_34") (pintype "passive"))
      (node (ref "SV4") (pin "5") (pinfunction "5_5") (pintype "passive"))
      (node (ref "SV4") (pin "7") (pinfunction "7_7") (pintype "passive"))
      (node (ref "SV4") (pin "9") (pinfunction "9_9") (pintype "passive"))
      (node (ref "SV5") (pin "1") (pinfunction "1_1") (pintype "passive"))
      (node (ref "SV5") (pin "10") (pinfunction "10_10") (pintype "passive"))
      (node (ref "SV5") (pin "11") (pinfunction "11_11") (pintype "passive"))
      (node (ref "SV5") (pin "13") (pinfunction "13_13") (pintype "passive"))
      (node (ref "SV5") (pin "14") (pinfunction "14_14") (pintype "passive"))
      (node (ref "SV5") (pin "15") (pinfunction "15_15") (pintype "passive"))
      (node (ref "SV5") (pin "17") (pinfunction "17_17") (pintype "passive"))
      (node (ref "SV5") (pin "18") (pinfunction "18_18") (pintype "passive"))
      (node (ref "SV5") (pin "19") (pinfunction "19_19") (pintype "passive"))
      (node (ref "SV5") (pin "21") (pinfunction "21_21") (pintype "passive"))
      (node (ref "SV5") (pin "22") (pinfunction "22_22") (pintype "passive"))
      (node (ref "SV5") (pin "23") (pinfunction "23_23") (pintype "passive"))
      (node (ref "SV5") (pin "25") (pinfunction "25_25") (pintype "passive"))
      (node (ref "SV5") (pin "26") (pinfunction "26_26") (pintype "passive"))
      (node (ref "SV5") (pin "27") (pinfunction "27_27") (pintype "passive"))
      (node (ref "SV5") (pin "29") (pinfunction "29_29") (pintype "passive"))
      (node (ref "SV5") (pin "3") (pinfunction "3_3") (pintype "passive"))
      (node (ref "SV5") (pin "31") (pinfunction "31_31") (pintype "passive"))
      (node (ref "SV5") (pin "33") (pinfunction "33_33") (pintype "passive"))
      (node (ref "SV5") (pin "34") (pinfunction "34_34") (pintype "passive"))
      (node (ref "SV5") (pin "5") (pinfunction "5_5") (pintype "passive"))
      (node (ref "SV5") (pin "7") (pinfunction "7_7") (pintype "passive"))
      (node (ref "SV5") (pin "9") (pinfunction "9_9") (pintype "passive"))
      (node (ref "SV6") (pin "A") (pinfunction "1_A") (pintype "bidirectional"))
      (node (ref "SV6") (pin "AA") (pinfunction "23_AA") (pintype "bidirectional"))
      (node (ref "SV6") (pin "B") (pinfunction "2_B") (pintype "bidirectional"))
      (node (ref "SV6") (pin "C") (pinfunction "3_C") (pintype "bidirectional"))
      (node (ref "SV6") (pin "CC") (pinfunction "25_CC") (pintype "bidirectional"))
      (node (ref "SV6") (pin "E") (pinfunction "5_E") (pintype "bidirectional"))
      (node (ref "SV6") (pin "EE") (pinfunction "27_EE") (pintype "bidirectional"))
      (node (ref "SV6") (pin "H") (pinfunction "7_H") (pintype "bidirectional"))
      (node (ref "SV6") (pin "HH") (pinfunction "29_HH") (pintype "bidirectional"))
      (node (ref "SV6") (pin "K") (pinfunction "9_K") (pintype "bidirectional"))
      (node (ref "SV6") (pin "KK") (pinfunction "31_KK") (pintype "bidirectional"))
      (node (ref "SV6") (pin "M") (pinfunction "11_M") (pintype "bidirectional"))
      (node (ref "SV6") (pin "MM") (pinfunction "33_MM") (pintype "bidirectional"))
      (node (ref "SV6") (pin "P") (pinfunction "13_P") (pintype "bidirectional"))
      (node (ref "SV6") (pin "PP") (pinfunction "35_PP") (pintype "bidirectional"))
      (node (ref "SV6") (pin "S") (pinfunction "15_S") (pintype "bidirectional"))
      (node (ref "SV6") (pin "SS") (pinfunction "37_SS") (pintype "bidirectional"))
      (node (ref "SV6") (pin "U") (pinfunction "17_U") (pintype "bidirectional"))
      (node (ref "SV6") (pin "UU") (pinfunction "39_UU") (pintype "bidirectional"))
      (node (ref "SV6") (pin "VV") (pinfunction "40_VV") (pintype "bidirectional"))
      (node (ref "SV6") (pin "W") (pinfunction "19_W") (pintype "bidirectional"))
      (node (ref "SV6") (pin "Y") (pinfunction "21_Y") (pintype "bidirectional"))
      (node (ref "SV7") (pin "1") (pinfunction "1_1") (pintype "passive"))
      (node (ref "SV7") (pin "10") (pinfunction "10_10") (pintype "passive"))
      (node (ref "SV7") (pin "11") (pinfunction "11_11") (pintype "passive"))
      (node (ref "SV7") (pin "13") (pinfunction "13_13") (pintype "passive"))
      (node (ref "SV7") (pin "14") (pinfunction "14_14") (pintype "passive"))
      (node (ref "SV7") (pin "15") (pinfunction "15_15") (pintype "passive"))
      (node (ref "SV7") (pin "17") (pinfunction "17_17") (pintype "passive"))
      (node (ref "SV7") (pin "18") (pinfunction "18_18") (pintype "passive"))
      (node (ref "SV7") (pin "19") (pinfunction "19_19") (pintype "passive"))
      (node (ref "SV7") (pin "21") (pinfunction "21_21") (pintype "passive"))
      (node (ref "SV7") (pin "22") (pinfunction "22_22") (pintype "passive"))
      (node (ref "SV7") (pin "23") (pinfunction "23_23") (pintype "passive"))
      (node (ref "SV7") (pin "25") (pinfunction "25_25") (pintype "passive"))
      (node (ref "SV7") (pin "26") (pinfunction "26_26") (pintype "passive"))
      (node (ref "SV7") (pin "27") (pinfunction "27_27") (pintype "passive"))
      (node (ref "SV7") (pin "29") (pinfunction "29_29") (pintype "passive"))
      (node (ref "SV7") (pin "3") (pinfunction "3_3") (pintype "passive"))
      (node (ref "SV7") (pin "31") (pinfunction "31_31") (pintype "passive"))
      (node (ref "SV7") (pin "33") (pinfunction "33_33") (pintype "passive"))
      (node (ref "SV7") (pin "34") (pinfunction "34_34") (pintype "passive"))
      (node (ref "SV7") (pin "5") (pinfunction "5_5") (pintype "passive"))
      (node (ref "SV7") (pin "7") (pinfunction "7_7") (pintype "passive"))
      (node (ref "SV7") (pin "9") (pinfunction "9_9") (pintype "passive"))
      (node (ref "SV8") (pin "1") (pinfunction "1_1") (pintype "passive"))
      (node (ref "SV8") (pin "10") (pinfunction "10_10") (pintype "passive"))
      (node (ref "SV8") (pin "11") (pinfunction "11_11") (pintype "passive"))
      (node (ref "SV8") (pin "13") (pinfunction "13_13") (pintype "passive"))
      (node (ref "SV8") (pin "14") (pinfunction "14_14") (pintype "passive"))
      (node (ref "SV8") (pin "15") (pinfunction "15_15") (pintype "passive"))
      (node (ref "SV8") (pin "17") (pinfunction "17_17") (pintype "passive"))
      (node (ref "SV8") (pin "18") (pinfunction "18_18") (pintype "passive"))
      (node (ref "SV8") (pin "19") (pinfunction "19_19") (pintype "passive"))
      (node (ref "SV8") (pin "21") (pinfunction "21_21") (pintype "passive"))
      (node (ref "SV8") (pin "22") (pinfunction "22_22") (pintype "passive"))
      (node (ref "SV8") (pin "23") (pinfunction "23_23") (pintype "passive"))
      (node (ref "SV8") (pin "25") (pinfunction "25_25") (pintype "passive"))
      (node (ref "SV8") (pin "26") (pinfunction "26_26") (pintype "passive"))
      (node (ref "SV8") (pin "27") (pinfunction "27_27") (pintype "passive"))
      (node (ref "SV8") (pin "29") (pinfunction "29_29") (pintype "passive"))
      (node (ref "SV8") (pin "3") (pinfunction "3_3") (pintype "passive"))
      (node (ref "SV8") (pin "31") (pinfunction "31_31") (pintype "passive"))
      (node (ref "SV8") (pin "33") (pinfunction "33_33") (pintype "passive"))
      (node (ref "SV8") (pin "34") (pinfunction "34_34") (pintype "passive"))
      (node (ref "SV8") (pin "5") (pinfunction "5_5") (pintype "passive"))
      (node (ref "SV8") (pin "7") (pinfunction "7_7") (pintype "passive"))
      (node (ref "SV8") (pin "9") (pinfunction "9_9") (pintype "passive"))
      (node (ref "SV9") (pin "A") (pinfunction "1_A") (pintype "bidirectional"))
      (node (ref "SV9") (pin "AA") (pinfunction "23_AA") (pintype "bidirectional"))
      (node (ref "SV9") (pin "B") (pinfunction "2_B") (pintype "bidirectional"))
      (node (ref "SV9") (pin "C") (pinfunction "3_C") (pintype "bidirectional"))
      (node (ref "SV9") (pin "CC") (pinfunction "25_CC") (pintype "bidirectional"))
      (node (ref "SV9") (pin "E") (pinfunction "5_E") (pintype "bidirectional"))
      (node (ref "SV9") (pin "EE") (pinfunction "27_EE") (pintype "bidirectional"))
      (node (ref "SV9") (pin "H") (pinfunction "7_H") (pintype "bidirectional"))
      (node (ref "SV9") (pin "HH") (pinfunction "29_HH") (pintype "bidirectional"))
      (node (ref "SV9") (pin "K") (pinfunction "9_K") (pintype "bidirectional"))
      (node (ref "SV9") (pin "KK") (pinfunction "31_KK") (pintype "bidirectional"))
      (node (ref "SV9") (pin "M") (pinfunction "11_M") (pintype "bidirectional"))
      (node (ref "SV9") (pin "MM") (pinfunction "33_MM") (pintype "bidirectional"))
      (node (ref "SV9") (pin "P") (pinfunction "13_P") (pintype "bidirectional"))
      (node (ref "SV9") (pin "PP") (pinfunction "35_PP") (pintype "bidirectional"))
      (node (ref "SV9") (pin "S") (pinfunction "15_S") (pintype "bidirectional"))
      (node (ref "SV9") (pin "SS") (pinfunction "37_SS") (pintype "bidirectional"))
      (node (ref "SV9") (pin "U") (pinfunction "17_U") (pintype "bidirectional"))
      (node (ref "SV9") (pin "UU") (pinfunction "39_UU") (pintype "bidirectional"))
      (node (ref "SV9") (pin "VV") (pinfunction "40_VV") (pintype "bidirectional"))
      (node (ref "SV9") (pin "W") (pinfunction "19_W") (pintype "bidirectional"))
      (node (ref "SV9") (pin "Y") (pinfunction "21_Y") (pintype "bidirectional"))
      (node (ref "X1") (pin "5") (pinfunction "5_5") (pintype "passive"))
      (node (ref "XESS") (pin "52") (pinfunction "GND_52") (pintype "power_in"))
    )
    (net (code "63") (name "IOP") (class "Default")
      (node (ref "E26") (pin "12") (pinfunction "O_12") (pintype "output"))
      (node (ref "E26") (pin "5") (pinfunction "I2_5") (pintype "input"))
    )
    (net (code "64") (name "IOP1") (class "Default")
      (node (ref "E29") (pin "4") (pinfunction "O_4") (pintype "output"))
      (node (ref "E3") (pin "1") (pinfunction "I0_1") (pintype "input"))
    )
    (net (code "65") (name "IOP1L") (class "Default")
      (node (ref "E26") (pin "1") (pinfunction "I0_1") (pintype "input"))
      (node (ref "E28") (pin "6") (pinfunction "Y2_6") (pintype "output"))
      (node (ref "E29") (pin "3") (pinfunction "I_3") (pintype "input"))
    )
    (net (code "66") (name "IOP2") (class "Default")
      (node (ref "E29") (pin "8") (pinfunction "O_8") (pintype "output"))
      (node (ref "E3") (pin "6") (pinfunction "I0_6") (pintype "input"))
    )
    (net (code "67") (name "IOP2L") (class "Default")
      (node (ref "E26") (pin "2") (pinfunction "I1_2") (pintype "input"))
      (node (ref "E28") (pin "11") (pinfunction "Y1_11") (pintype "output"))
      (node (ref "E29") (pin "9") (pinfunction "I_9") (pintype "input"))
    )
    (net (code "68") (name "IOP4") (class "Default")
      (node (ref "E2") (pin "1") (pinfunction "I0_1") (pintype "input"))
      (node (ref "E29") (pin "10") (pinfunction "O_10") (pintype "output"))
    )
    (net (code "69") (name "IOP4L") (class "Default")
      (node (ref "E26") (pin "13") (pinfunction "I2_13") (pintype "input"))
      (node (ref "E28") (pin "10") (pinfunction "Y2_10") (pintype "output"))
      (node (ref "E29") (pin "11") (pinfunction "I_11") (pintype "input"))
    )
    (net (code "70") (name "IOPL") (class "Default")
      (node (ref "E25") (pin "1") (pinfunction "G_1") (pintype "input"))
      (node (ref "E26") (pin "6") (pinfunction "O_6") (pintype "output"))
      (node (ref "E27") (pin "1") (pinfunction "G_1") (pintype "input"))
      (node (ref "E27") (pin "19") (pinfunction "G_19") (pintype "input"))
    )
    (net (code "71") (name "IRQ") (class "Default")
      (node (ref "D15") (pin "A") (pinfunction "A_A") (pintype "passive"))
      (node (ref "RN2") (pin "14") (pinfunction "2_14") (pintype "passive"))
      (node (ref "XESS") (pin "36") (pinfunction "G1_36") (pintype "bidirectional"))
    )
    (net (code "72") (name "MX_0") (class "Default")
      (node (ref "E28") (pin "2") (pinfunction "A_2") (pintype "input"))
      (node (ref "XESS") (pin "57") (pinfunction "L5_57") (pintype "bidirectional"))
    )
    (net (code "73") (name "MX_1") (class "Default")
      (node (ref "E28") (pin "3") (pinfunction "B_3") (pintype "input"))
      (node (ref "XESS") (pin "56") (pinfunction "N2_56") (pintype "bidirectional"))
    )
    (net (code "74") (name "MX_2") (class "Default")
      (node (ref "E28") (pin "14") (pinfunction "A_14") (pintype "input"))
      (node (ref "XESS") (pin "51") (pinfunction "M3_51") (pintype "bidirectional"))
    )
    (net (code "75") (name "MX_3") (class "Default")
      (node (ref "E28") (pin "13") (pinfunction "B_13") (pintype "input"))
      (node (ref "XESS") (pin "50") (pinfunction "N1_50") (pintype "bidirectional"))
    )
    (net (code "76") (name "Net-(E1A-1Q)") (class "Default")
      (node (ref "E1") (pin "2") (pinfunction "1Q_2") (pintype "tri_state"))
      (node (ref "E7") (pin "1") (pinfunction "I0_1") (pintype "input"))
    )
    (net (code "77") (name "Net-(E1A-2Q)") (class "Default")
      (node (ref "E1") (pin "5") (pinfunction "2Q_5") (pintype "tri_state"))
      (node (ref "E7") (pin "6") (pinfunction "I0_6") (pintype "input"))
    )
    (net (code "78") (name "Net-(E1A-3Q)") (class "Default")
      (node (ref "E1") (pin "6") (pinfunction "3Q_6") (pintype "tri_state"))
      (node (ref "E6") (pin "1") (pinfunction "I0_1") (pintype "input"))
    )
    (net (code "79") (name "Net-(E1A-4Q)") (class "Default")
      (node (ref "E1") (pin "9") (pinfunction "4Q_9") (pintype "tri_state"))
      (node (ref "E6") (pin "6") (pinfunction "I0_6") (pintype "input"))
    )
    (net (code "80") (name "Net-(E1A-5Q)") (class "Default")
      (node (ref "E1") (pin "12") (pinfunction "5Q_12") (pintype "tri_state"))
      (node (ref "E8") (pin "1") (pinfunction "I0_1") (pintype "input"))
    )
    (net (code "81") (name "Net-(E1A-6Q)") (class "Default")
      (node (ref "E1") (pin "15") (pinfunction "6Q_15") (pintype "tri_state"))
      (node (ref "E8") (pin "6") (pinfunction "I0_6") (pintype "input"))
    )
    (net (code "82") (name "Net-(E10A-I0)") (class "Default")
      (node (ref "E10") (pin "1") (pinfunction "I0_1") (pintype "input"))
      (node (ref "E12") (pin "12") (pinfunction "5Q_12") (pintype "tri_state"))
    )
    (net (code "83") (name "Net-(E10B-I0)") (class "Default")
      (node (ref "E10") (pin "6") (pinfunction "I0_6") (pintype "input"))
      (node (ref "E12") (pin "15") (pinfunction "6Q_15") (pintype "tri_state"))
    )
    (net (code "84") (name "Net-(E11A-I0)") (class "Default")
      (node (ref "E11") (pin "1") (pinfunction "I0_1") (pintype "input"))
      (node (ref "E12") (pin "2") (pinfunction "1Q_2") (pintype "tri_state"))
    )
    (net (code "85") (name "Net-(E11B-I0)") (class "Default")
      (node (ref "E11") (pin "6") (pinfunction "I0_6") (pintype "input"))
      (node (ref "E12") (pin "5") (pinfunction "2Q_5") (pintype "tri_state"))
    )
    (net (code "86") (name "Net-(E12A-3Q)") (class "Default")
      (node (ref "E12") (pin "6") (pinfunction "3Q_6") (pintype "tri_state"))
      (node (ref "E9") (pin "1") (pinfunction "I0_1") (pintype "input"))
    )
    (net (code "87") (name "Net-(E12A-4Q)") (class "Default")
      (node (ref "E12") (pin "9") (pinfunction "4Q_9") (pintype "tri_state"))
      (node (ref "E9") (pin "6") (pinfunction "I0_6") (pintype "input"))
    )
    (net (code "88") (name "Net-(E13A-1Q)") (class "Default")
      (node (ref "E13") (pin "2") (pinfunction "1Q_2") (pintype "tri_state"))
      (node (ref "E16") (pin "1") (pinfunction "I0_1") (pintype "input"))
    )
    (net (code "89") (name "Net-(E13A-2Q)") (class "Default")
      (node (ref "E13") (pin "5") (pinfunction "2Q_5") (pintype "tri_state"))
      (node (ref "E16") (pin "6") (pinfunction "I0_6") (pintype "input"))
    )
    (net (code "90") (name "Net-(E13A-3Q)") (class "Default")
      (node (ref "E13") (pin "6") (pinfunction "3Q_6") (pintype "tri_state"))
      (node (ref "E15") (pin "1") (pinfunction "I0_1") (pintype "input"))
    )
    (net (code "91") (name "Net-(E13A-4Q)") (class "Default")
      (node (ref "E13") (pin "9") (pinfunction "4Q_9") (pintype "tri_state"))
      (node (ref "E15") (pin "6") (pinfunction "I0_6") (pintype "input"))
    )
    (net (code "92") (name "Net-(E13A-5Q)") (class "Default")
      (node (ref "E13") (pin "12") (pinfunction "5Q_12") (pintype "tri_state"))
      (node (ref "E14") (pin "1") (pinfunction "I0_1") (pintype "input"))
    )
    (net (code "93") (name "Net-(E13A-6Q)") (class "Default")
      (node (ref "E13") (pin "15") (pinfunction "6Q_15") (pintype "tri_state"))
      (node (ref "E14") (pin "6") (pinfunction "I0_6") (pintype "input"))
    )
    (net (code "94") (name "Net-(E20A-I0)") (class "Default")
      (node (ref "E20") (pin "1") (pinfunction "I0_1") (pintype "input"))
      (node (ref "E23") (pin "12") (pinfunction "5Q_12") (pintype "tri_state"))
    )
    (net (code "95") (name "Net-(E20B-I0)") (class "Default")
      (node (ref "E20") (pin "6") (pinfunction "I0_6") (pintype "input"))
      (node (ref "E23") (pin "15") (pinfunction "6Q_15") (pintype "tri_state"))
    )
    (net (code "96") (name "Net-(E21A-I0)") (class "Default")
      (node (ref "E21") (pin "1") (pinfunction "I0_1") (pintype "input"))
      (node (ref "E23") (pin "6") (pinfunction "3Q_6") (pintype "tri_state"))
    )
    (net (code "97") (name "Net-(E21B-I0)") (class "Default")
      (node (ref "E21") (pin "6") (pinfunction "I0_6") (pintype "input"))
      (node (ref "E23") (pin "9") (pinfunction "4Q_9") (pintype "tri_state"))
    )
    (net (code "98") (name "Net-(E22A-I0)") (class "Default")
      (node (ref "E22") (pin "1") (pinfunction "I0_1") (pintype "input"))
      (node (ref "E23") (pin "2") (pinfunction "1Q_2") (pintype "tri_state"))
    )
    (net (code "99") (name "Net-(E22B-I0)") (class "Default")
      (node (ref "E22") (pin "6") (pinfunction "I0_6") (pintype "input"))
      (node (ref "E23") (pin "5") (pinfunction "2Q_5") (pintype "tri_state"))
    )
    (net (code "100") (name "Net-(E24A-C1+)") (class "Default")
      (node (ref "C40") (pin "1") (pinfunction "1_1") (pintype "passive"))
      (node (ref "E24") (pin "1") (pinfunction "C1+_1") (pintype "bidirectional"))
    )
    (net (code "101") (name "Net-(E24A-C1-)") (class "Default")
      (node (ref "C40") (pin "2") (pinfunction "2_2") (pintype "passive"))
      (node (ref "E24") (pin "3") (pinfunction "C1-_3") (pintype "bidirectional"))
    )
    (net (code "102") (name "Net-(E24A-C2+)") (class "Default")
      (node (ref "C42") (pin "1") (pinfunction "1_1") (pintype "passive"))
      (node (ref "E24") (pin "4") (pinfunction "C2+_4") (pintype "bidirectional"))
    )
    (net (code "103") (name "Net-(E24A-C2-)") (class "Default")
      (node (ref "C42") (pin "2") (pinfunction "2_2") (pintype "passive"))
      (node (ref "E24") (pin "5") (pinfunction "C2-_5") (pintype "bidirectional"))
    )
    (net (code "104") (name "Net-(E24A-R1IN)") (class "Default")
      (node (ref "E24") (pin "13") (pinfunction "R1IN_13") (pintype "input"))
      (node (ref "X1") (pin "3") (pinfunction "3_3") (pintype "passive"))
    )
    (net (code "105") (name "Net-(E24A-T1OUT)") (class "Default")
      (node (ref "E24") (pin "14") (pinfunction "T1OUT_14") (pintype "output"))
      (node (ref "X1") (pin "2") (pinfunction "2_2") (pintype "passive"))
    )
    (net (code "106") (name "Net-(E24A-T2OUT)") (class "Default")
      (node (ref "E24") (pin "7") (pinfunction "T2OUT_7") (pintype "output"))
      (node (ref "X1") (pin "8") (pinfunction "8_8") (pintype "passive"))
    )
    (net (code "107") (name "Net-(E24A-V+)") (class "Default")
      (node (ref "C41") (pin "1") (pinfunction "1_1") (pintype "passive"))
      (node (ref "E24") (pin "2") (pinfunction "V+_2") (pintype "bidirectional"))
    )
    (net (code "108") (name "Net-(E24A-V-)") (class "Default")
      (node (ref "C43") (pin "2") (pinfunction "2_2") (pintype "passive"))
      (node (ref "E24") (pin "6") (pinfunction "V-_6") (pintype "bidirectional"))
    )
    (net (code "109") (name "Net-(E25A-Y1)") (class "Default")
      (node (ref "E25") (pin "18") (pinfunction "Y1_18") (pintype "tri_state"))
      (node (ref "RN2") (pin "2") (pinfunction "1_2") (pintype "passive"))
    )
    (net (code "110") (name "Net-(E25A-Y2)") (class "Default")
      (node (ref "E25") (pin "16") (pinfunction "Y2_16") (pintype "tri_state"))
      (node (ref "RN2") (pin "4") (pinfunction "1_4") (pintype "passive"))
    )
    (net (code "111") (name "Net-(E25A-Y3)") (class "Default")
      (node (ref "E25") (pin "14") (pinfunction "Y3_14") (pintype "tri_state"))
      (node (ref "RN2") (pin "6") (pinfunction "1_6") (pintype "passive"))
    )
    (net (code "112") (name "Net-(E25A-Y4)") (class "Default")
      (node (ref "E25") (pin "12") (pinfunction "Y4_12") (pintype "tri_state"))
      (node (ref "RN2") (pin "8") (pinfunction "1_8") (pintype "passive"))
    )
    (net (code "113") (name "Net-(E25B-Y1)") (class "Default")
      (node (ref "E25") (pin "9") (pinfunction "Y1_9") (pintype "tri_state"))
      (node (ref "RN2") (pin "7") (pinfunction "1_7") (pintype "passive"))
    )
    (net (code "114") (name "Net-(E25B-Y2)") (class "Default")
      (node (ref "E25") (pin "7") (pinfunction "Y2_7") (pintype "tri_state"))
      (node (ref "RN2") (pin "5") (pinfunction "1_5") (pintype "passive"))
    )
    (net (code "115") (name "Net-(E25B-Y3)") (class "Default")
      (node (ref "E25") (pin "5") (pinfunction "Y3_5") (pintype "tri_state"))
      (node (ref "RN2") (pin "3") (pinfunction "1_3") (pintype "passive"))
    )
    (net (code "116") (name "Net-(E25B-Y4)") (class "Default")
      (node (ref "E25") (pin "3") (pinfunction "Y4_3") (pintype "tri_state"))
      (node (ref "RN2") (pin "1") (pinfunction "1_1") (pintype "passive"))
    )
    (net (code "117") (name "Net-(E27A-Y1)") (class "Default")
      (node (ref "E27") (pin "18") (pinfunction "Y1_18") (pintype "tri_state"))
      (node (ref "RN1") (pin "1") (pinfunction "1_1") (pintype "passive"))
    )
    (net (code "118") (name "Net-(E27A-Y2)") (class "Default")
      (node (ref "E27") (pin "16") (pinfunction "Y2_16") (pintype "tri_state"))
      (node (ref "RN1") (pin "3") (pinfunction "1_3") (pintype "passive"))
    )
    (net (code "119") (name "Net-(E27A-Y3)") (class "Default")
      (node (ref "E27") (pin "14") (pinfunction "Y3_14") (pintype "tri_state"))
      (node (ref "RN1") (pin "5") (pinfunction "1_5") (pintype "passive"))
    )
    (net (code "120") (name "Net-(E27A-Y4)") (class "Default")
      (node (ref "E27") (pin "12") (pinfunction "Y4_12") (pintype "tri_state"))
      (node (ref "RN1") (pin "7") (pinfunction "1_7") (pintype "passive"))
    )
    (net (code "121") (name "Net-(E27B-Y1)") (class "Default")
      (node (ref "E27") (pin "9") (pinfunction "Y1_9") (pintype "tri_state"))
      (node (ref "RN1") (pin "8") (pinfunction "1_8") (pintype "passive"))
    )
    (net (code "122") (name "Net-(E27B-Y2)") (class "Default")
      (node (ref "E27") (pin "7") (pinfunction "Y2_7") (pintype "tri_state"))
      (node (ref "RN1") (pin "6") (pinfunction "1_6") (pintype "passive"))
    )
    (net (code "123") (name "Net-(E27B-Y3)") (class "Default")
      (node (ref "E27") (pin "5") (pinfunction "Y3_5") (pintype "tri_state"))
      (node (ref "RN1") (pin "4") (pinfunction "1_4") (pintype "passive"))
    )
    (net (code "124") (name "Net-(E27B-Y4)") (class "Default")
      (node (ref "E27") (pin "3") (pinfunction "Y4_3") (pintype "tri_state"))
      (node (ref "RN1") (pin "2") (pinfunction "1_2") (pintype "passive"))
    )
    (net (code "125") (name "Net-(E28A-G)") (class "Default")
      (node (ref "E28") (pin "1") (pinfunction "G_1") (pintype "input"))
      (node (ref "E28") (pin "12") (pinfunction "Y0_12") (pintype "output"))
    )
    (net (code "126") (name "Net-(FUSE-Pad1)") (class "Default")
      (node (ref "FUSE") (pin "1") (pinfunction "1_1") (pintype "passive"))
      (node (ref "J2") (pin "4") (pinfunction "4_4") (pintype "passive"))
    )
    (net (code "127") (name "Net-(RN2A-2)") (class "Default")
      (node (ref "D16") (pin "A") (pinfunction "A_A") (pintype "passive"))
      (node (ref "RN2") (pin "16") (pinfunction "2_16") (pintype "passive"))
    )
    (net (code "128") (name "PD_0") (class "Default")
      (node (ref "D1") (pin "A") (pinfunction "A_A") (pintype "passive"))
      (node (ref "E12") (pin "3") (pinfunction "1D_3") (pintype "input"))
      (node (ref "E23") (pin "3") (pinfunction "1D_3") (pintype "input"))
      (node (ref "RN1") (pin "16") (pinfunction "2_16") (pintype "passive"))
      (node (ref "XESS") (pin "71") (pinfunction "P12_71") (pintype "bidirectional"))
    )
    (net (code "129") (name "PD_1") (class "Default")
      (node (ref "D2") (pin "A") (pinfunction "A_A") (pintype "passive"))
      (node (ref "E12") (pin "4") (pinfunction "2D_4") (pintype "input"))
      (node (ref "E23") (pin "4") (pinfunction "2D_4") (pintype "input"))
      (node (ref "RN1") (pin "14") (pinfunction "2_14") (pintype "passive"))
      (node (ref "XESS") (pin "40") (pinfunction "J1_40") (pintype "bidirectional"))
    )
    (net (code "130") (name "PD_2") (class "Default")
      (node (ref "D3") (pin "A") (pinfunction "A_A") (pintype "passive"))
      (node (ref "E12") (pin "7") (pinfunction "3D_7") (pintype "input"))
      (node (ref "E23") (pin "7") (pinfunction "3D_7") (pintype "input"))
      (node (ref "RN1") (pin "12") (pinfunction "2_12") (pintype "passive"))
      (node (ref "XESS") (pin "39") (pinfunction "H1_39") (pintype "bidirectional"))
    )
    (net (code "131") (name "PD_3") (class "Default")
      (node (ref "D4") (pin "A") (pinfunction "A_A") (pintype "passive"))
      (node (ref "E12") (pin "8") (pinfunction "4D_8") (pintype "input"))
      (node (ref "E23") (pin "8") (pinfunction "4D_8") (pintype "input"))
      (node (ref "RN1") (pin "10") (pinfunction "2_10") (pintype "passive"))
      (node (ref "XESS") (pin "38") (pinfunction "H3_38") (pintype "bidirectional"))
    )
    (net (code "132") (name "PD_4") (class "Default")
      (node (ref "D5") (pin "A") (pinfunction "A_A") (pintype "passive"))
      (node (ref "E12") (pin "13") (pinfunction "5D_13") (pintype "input"))
      (node (ref "E23") (pin "13") (pinfunction "5D_13") (pintype "input"))
      (node (ref "RN1") (pin "9") (pinfunction "2_9") (pintype "passive"))
      (node (ref "XESS") (pin "35") (pinfunction "G2_35") (pintype "bidirectional"))
    )
    (net (code "133") (name "PD_5") (class "Default")
      (node (ref "D6") (pin "A") (pinfunction "A_A") (pintype "passive"))
      (node (ref "E12") (pin "14") (pinfunction "6D_14") (pintype "input"))
      (node (ref "E23") (pin "14") (pinfunction "6D_14") (pintype "input"))
      (node (ref "RN1") (pin "11") (pinfunction "2_11") (pintype "passive"))
      (node (ref "XESS") (pin "80") (pinfunction "K15_80") (pintype "bidirectional"))
    )
    (net (code "134") (name "PD_6") (class "Default")
      (node (ref "D7") (pin "A") (pinfunction "A_A") (pintype "passive"))
      (node (ref "E1") (pin "3") (pinfunction "1D_3") (pintype "input"))
      (node (ref "E13") (pin "3") (pinfunction "1D_3") (pintype "input"))
      (node (ref "RN1") (pin "13") (pinfunction "2_13") (pintype "passive"))
      (node (ref "XESS") (pin "81") (pinfunction "K16_81") (pintype "bidirectional"))
    )
    (net (code "135") (name "PD_7") (class "Default")
      (node (ref "D8") (pin "A") (pinfunction "A_A") (pintype "passive"))
      (node (ref "E1") (pin "4") (pinfunction "2D_4") (pintype "input"))
      (node (ref "E13") (pin "4") (pinfunction "2D_4") (pintype "input"))
      (node (ref "RN1") (pin "15") (pinfunction "2_15") (pintype "passive"))
      (node (ref "XESS") (pin "10") (pinfunction "F15_10") (pintype "bidirectional"))
    )
    (net (code "136") (name "PD_8") (class "Default")
      (node (ref "D9") (pin "A") (pinfunction "A_A") (pintype "passive"))
      (node (ref "E1") (pin "7") (pinfunction "3D_7") (pintype "input"))
      (node (ref "E13") (pin "7") (pinfunction "3D_7") (pintype "input"))
      (node (ref "RN2") (pin "15") (pinfunction "2_15") (pintype "passive"))
      (node (ref "XESS") (pin "27") (pinfunction "E2_27") (pintype "bidirectional"))
    )
    (net (code "137") (name "PD_9") (class "Default")
      (node (ref "D10") (pin "A") (pinfunction "A_A") (pintype "passive"))
      (node (ref "E1") (pin "8") (pinfunction "4D_8") (pintype "input"))
      (node (ref "E13") (pin "8") (pinfunction "4D_8") (pintype "input"))
      (node (ref "RN2") (pin "13") (pinfunction "2_13") (pintype "passive"))
      (node (ref "XESS") (pin "28") (pinfunction "E1_28") (pintype "bidirectional"))
    )
    (net (code "138") (name "PD_10") (class "Default")
      (node (ref "D11") (pin "A") (pinfunction "A_A") (pintype "passive"))
      (node (ref "E1") (pin "13") (pinfunction "5D_13") (pintype "input"))
      (node (ref "E13") (pin "13") (pinfunction "5D_13") (pintype "input"))
      (node (ref "RN2") (pin "11") (pinfunction "2_11") (pintype "passive"))
      (node (ref "XESS") (pin "29") (pinfunction "F3_29") (pintype "bidirectional"))
    )
    (net (code "139") (name "PD_11") (class "Default")
      (node (ref "D12") (pin "A") (pinfunction "A_A") (pintype "passive"))
      (node (ref "E1") (pin "14") (pinfunction "6D_14") (pintype "input"))
      (node (ref "E13") (pin "14") (pinfunction "6D_14") (pintype "input"))
      (node (ref "RN2") (pin "9") (pinfunction "2_9") (pintype "passive"))
      (node (ref "XESS") (pin "32") (pinfunction "F2_32") (pintype "bidirectional"))
    )
    (net (code "140") (name "RTS") (class "Default")
      (node (ref "E24") (pin "10") (pinfunction "T2IN_10") (pintype "input"))
      (node (ref "XESS") (pin "26") (pinfunction "F4_26") (pintype "bidirectional"))
    )
    (net (code "141") (name "RUN") (class "Default")
      (node (ref "E4") (pin "1") (pinfunction "I0_1") (pintype "input"))
      (node (ref "XESS") (pin "70") (pinfunction "T13_70") (pintype "bidirectional"))
    )
    (net (code "142") (name "RXD") (class "Default")
      (node (ref "E24") (pin "12") (pinfunction "R1OUT_12") (pintype "output"))
      (node (ref "XESS") (pin "31") (pinfunction "G5_31") (pintype "bidirectional"))
    )
    (net (code "143") (name "SKIP") (class "Default")
      (node (ref "D13") (pin "A") (pinfunction "A_A") (pintype "passive"))
      (node (ref "RN2") (pin "10") (pinfunction "2_10") (pintype "passive"))
      (node (ref "XESS") (pin "37") (pinfunction "H4_37") (pintype "bidirectional"))
    )
    (net (code "144") (name "T2") (class "Default")
      (node (ref "R52") (pin "1") (pinfunction "1_1") (pintype "passive"))
      (node (ref "SV1") (pin "30") (pinfunction "30_30") (pintype "passive"))
      (node (ref "SV3") (pin "NN") (pinfunction "34_NN") (pintype "bidirectional"))
    )
    (net (code "145") (name "TS1") (class "Default")
      (node (ref "E5") (pin "1") (pinfunction "I0_1") (pintype "input"))
      (node (ref "XESS") (pin "18") (pinfunction "E15_18") (pintype "bidirectional"))
    )
    (net (code "146") (name "TS3") (class "Default")
      (node (ref "E5") (pin "6") (pinfunction "I0_6") (pintype "input"))
      (node (ref "XESS") (pin "19") (pinfunction "D16_19") (pintype "bidirectional"))
    )
    (net (code "147") (name "TXD") (class "Default")
      (node (ref "E24") (pin "11") (pinfunction "T1IN_11") (pintype "input"))
      (node (ref "XESS") (pin "41") (pinfunction "J2_41") (pintype "bidirectional"))
    )
    (net (code "148") (name "V2") (class "Default")
      (node (ref "R54") (pin "1") (pinfunction "1_1") (pintype "passive"))
      (node (ref "SV1") (pin "32") (pinfunction "32_32") (pintype "passive"))
      (node (ref "SV3") (pin "TT") (pinfunction "38_TT") (pintype "bidirectional"))
    )
    (net (code "149") (name "VCC") (class "Default")
      (node (ref "C1") (pin "1") (pinfunction "1_1") (pintype "passive"))
      (node (ref "C10") (pin "1") (pinfunction "1_1") (pintype "passive"))
      (node (ref "C11") (pin "1") (pinfunction "1_1") (pintype "passive"))
      (node (ref "C12") (pin "1") (pinfunction "1_1") (pintype "passive"))
      (node (ref "C13") (pin "1") (pinfunction "1_1") (pintype "passive"))
      (node (ref "C14") (pin "1") (pinfunction "1_1") (pintype "passive"))
      (node (ref "C15") (pin "1") (pinfunction "1_1") (pintype "passive"))
      (node (ref "C16") (pin "1") (pinfunction "1_1") (pintype "passive"))
      (node (ref "C17") (pin "1") (pinfunction "1_1") (pintype "passive"))
      (node (ref "C18") (pin "1") (pinfunction "1_1") (pintype "passive"))
      (node (ref "C19") (pin "1") (pinfunction "1_1") (pintype "passive"))
      (node (ref "C2") (pin "1") (pinfunction "1_1") (pintype "passive"))
      (node (ref "C20") (pin "1") (pinfunction "1_1") (pintype "passive"))
      (node (ref "C21") (pin "1") (pinfunction "1_1") (pintype "passive"))
      (node (ref "C22") (pin "1") (pinfunction "1_1") (pintype "passive"))
      (node (ref "C23") (pin "1") (pinfunction "1_1") (pintype "passive"))
      (node (ref "C24") (pin "1") (pinfunction "1_1") (pintype "passive"))
      (node (ref "C25") (pin "1") (pinfunction "1_1") (pintype "passive"))
      (node (ref "C26") (pin "1") (pinfunction "1_1") (pintype "passive"))
      (node (ref "C27") (pin "1") (pinfunction "1_1") (pintype "passive"))
      (node (ref "C28") (pin "1") (pinfunction "1_1") (pintype "passive"))
      (node (ref "C29") (pin "1") (pinfunction "1_1") (pintype "passive"))
      (node (ref "C3") (pin "1") (pinfunction "1_1") (pintype "passive"))
      (node (ref "C38") (pin "+") (pinfunction "+_+") (pintype "passive"))
      (node (ref "C39") (pin "+") (pinfunction "+_+") (pintype "passive"))
      (node (ref "C4") (pin "1") (pinfunction "1_1") (pintype "passive"))
      (node (ref "C41") (pin "2") (pinfunction "2_2") (pintype "passive"))
      (node (ref "C5") (pin "1") (pinfunction "1_1") (pintype "passive"))
      (node (ref "C6") (pin "1") (pinfunction "1_1") (pintype "passive"))
      (node (ref "C7") (pin "1") (pinfunction "1_1") (pintype "passive"))
      (node (ref "C8") (pin "1") (pinfunction "1_1") (pintype "passive"))
      (node (ref "C9") (pin "1") (pinfunction "1_1") (pintype "passive"))
      (node (ref "E17") (pin "2") (pinfunction "I1_2") (pintype "input"))
      (node (ref "E17") (pin "7") (pinfunction "I1_7") (pintype "input"))
      (node (ref "E18") (pin "2") (pinfunction "I1_2") (pintype "input"))
      (node (ref "E18") (pin "7") (pinfunction "I1_7") (pintype "input"))
      (node (ref "E19") (pin "2") (pinfunction "I1_2") (pintype "input"))
      (node (ref "E19") (pin "7") (pinfunction "I1_7") (pintype "input"))
      (node (ref "E26") (pin "3") (pinfunction "I0_3") (pintype "input"))
      (node (ref "E26") (pin "4") (pinfunction "I1_4") (pintype "input"))
      (node (ref "FUSE") (pin "2") (pinfunction "2_2") (pintype "passive"))
      (node (ref "R1") (pin "2") (pinfunction "2_2") (pintype "passive"))
      (node (ref "R10") (pin "2") (pinfunction "2_2") (pintype "passive"))
      (node (ref "R11") (pin "2") (pinfunction "2_2") (pintype "passive"))
      (node (ref "R12") (pin "2") (pinfunction "2_2") (pintype "passive"))
      (node (ref "R13") (pin "2") (pinfunction "2_2") (pintype "passive"))
      (node (ref "R14") (pin "2") (pinfunction "2_2") (pintype "passive"))
      (node (ref "R15") (pin "2") (pinfunction "2_2") (pintype "passive"))
      (node (ref "R16") (pin "2") (pinfunction "2_2") (pintype "passive"))
      (node (ref "R17") (pin "2") (pinfunction "2_2") (pintype "passive"))
      (node (ref "R18") (pin "2") (pinfunction "2_2") (pintype "passive"))
      (node (ref "R19") (pin "2") (pinfunction "2_2") (pintype "passive"))
      (node (ref "R2") (pin "2") (pinfunction "2_2") (pintype "passive"))
      (node (ref "R20") (pin "2") (pinfunction "2_2") (pintype "passive"))
      (node (ref "R21") (pin "2") (pinfunction "2_2") (pintype "passive"))
      (node (ref "R22") (pin "2") (pinfunction "2_2") (pintype "passive"))
      (node (ref "R23") (pin "2") (pinfunction "2_2") (pintype "passive"))
      (node (ref "R24") (pin "2") (pinfunction "2_2") (pintype "passive"))
      (node (ref "R25") (pin "2") (pinfunction "2_2") (pintype "passive"))
      (node (ref "R26") (pin "2") (pinfunction "2_2") (pintype "passive"))
      (node (ref "R27") (pin "2") (pinfunction "2_2") (pintype "passive"))
      (node (ref "R28") (pin "2") (pinfunction "2_2") (pintype "passive"))
      (node (ref "R29") (pin "2") (pinfunction "2_2") (pintype "passive"))
      (node (ref "R3") (pin "2") (pinfunction "2_2") (pintype "passive"))
      (node (ref "R30") (pin "2") (pinfunction "2_2") (pintype "passive"))
      (node (ref "R31") (pin "2") (pinfunction "2_2") (pintype "passive"))
      (node (ref "R32") (pin "2") (pinfunction "2_2") (pintype "passive"))
      (node (ref "R33") (pin "2") (pinfunction "2_2") (pintype "passive"))
      (node (ref "R34") (pin "2") (pinfunction "2_2") (pintype "passive"))
      (node (ref "R35") (pin "2") (pinfunction "2_2") (pintype "passive"))
      (node (ref "R36") (pin "2") (pinfunction "2_2") (pintype "passive"))
      (node (ref "R37") (pin "2") (pinfunction "2_2") (pintype "passive"))
      (node (ref "R38") (pin "2") (pinfunction "2_2") (pintype "passive"))
      (node (ref "R39") (pin "2") (pinfunction "2_2") (pintype "passive"))
      (node (ref "R4") (pin "2") (pinfunction "2_2") (pintype "passive"))
      (node (ref "R40") (pin "2") (pinfunction "2_2") (pintype "passive"))
      (node (ref "R41") (pin "2") (pinfunction "2_2") (pintype "passive"))
      (node (ref "R42") (pin "2") (pinfunction "2_2") (pintype "passive"))
      (node (ref "R43") (pin "2") (pinfunction "2_2") (pintype "passive"))
      (node (ref "R44") (pin "2") (pinfunction "2_2") (pintype "passive"))
      (node (ref "R45") (pin "2") (pinfunction "2_2") (pintype "passive"))
      (node (ref "R46") (pin "2") (pinfunction "2_2") (pintype "passive"))
      (node (ref "R47") (pin "2") (pinfunction "2_2") (pintype "passive"))
      (node (ref "R48") (pin "2") (pinfunction "2_2") (pintype "passive"))
      (node (ref "R49") (pin "2") (pinfunction "2_2") (pintype "passive"))
      (node (ref "R5") (pin "2") (pinfunction "2_2") (pintype "passive"))
      (node (ref "R50") (pin "2") (pinfunction "2_2") (pintype "passive"))
      (node (ref "R51") (pin "2") (pinfunction "2_2") (pintype "passive"))
      (node (ref "R52") (pin "2") (pinfunction "2_2") (pintype "passive"))
      (node (ref "R53") (pin "2") (pinfunction "2_2") (pintype "passive"))
      (node (ref "R54") (pin "2") (pinfunction "2_2") (pintype "passive"))
      (node (ref "R6") (pin "2") (pinfunction "2_2") (pintype "passive"))
      (node (ref "R7") (pin "2") (pinfunction "2_2") (pintype "passive"))
      (node (ref "R8") (pin "2") (pinfunction "2_2") (pintype "passive"))
      (node (ref "R9") (pin "2") (pinfunction "2_2") (pintype "passive"))
    )
    (net (code "150") (name "unconnected-(E1A-7Q-Pad16)") (class "Default")
      (node (ref "E1") (pin "16") (pinfunction "7Q_16") (pintype "tri_state"))
    )
    (net (code "151") (name "unconnected-(E1A-8Q-Pad19)") (class "Default")
      (node (ref "E1") (pin "19") (pinfunction "8Q_19") (pintype "tri_state"))
    )
    (net (code "152") (name "unconnected-(E2B-O-Pad5)") (class "Default")
      (node (ref "E2") (pin "5") (pinfunction "O_5") (pintype "open_collector"))
    )
    (net (code "153") (name "unconnected-(E12A-7Q-Pad16)") (class "Default")
      (node (ref "E12") (pin "16") (pinfunction "7Q_16") (pintype "tri_state"))
    )
    (net (code "154") (name "unconnected-(E12A-8Q-Pad19)") (class "Default")
      (node (ref "E12") (pin "19") (pinfunction "8Q_19") (pintype "tri_state"))
    )
    (net (code "155") (name "unconnected-(E13A-7Q-Pad16)") (class "Default")
      (node (ref "E13") (pin "16") (pinfunction "7Q_16") (pintype "tri_state"))
    )
    (net (code "156") (name "unconnected-(E13A-8Q-Pad19)") (class "Default")
      (node (ref "E13") (pin "19") (pinfunction "8Q_19") (pintype "tri_state"))
    )
    (net (code "157") (name "unconnected-(E23A-7Q-Pad16)") (class "Default")
      (node (ref "E23") (pin "16") (pinfunction "7Q_16") (pintype "tri_state"))
    )
    (net (code "158") (name "unconnected-(E23A-8Q-Pad19)") (class "Default")
      (node (ref "E23") (pin "19") (pinfunction "8Q_19") (pintype "tri_state"))
    )
    (net (code "159") (name "unconnected-(E24A-R2OUT-Pad9)") (class "Default")
      (node (ref "E24") (pin "9") (pinfunction "R2OUT_9") (pintype "output"))
    )
    (net (code "160") (name "unconnected-(E28A-Y0-Pad4)") (class "Default")
      (node (ref "E28") (pin "4") (pinfunction "Y0_4") (pintype "output"))
    )
    (net (code "161") (name "unconnected-(E28B-Y3-Pad9)") (class "Default")
      (node (ref "E28") (pin "9") (pinfunction "Y3_9") (pintype "output"))
    )
    (net (code "162") (name "unconnected-(J2-Pad1)") (class "Default")
      (node (ref "J2") (pin "1") (pinfunction "1_1") (pintype "passive"))
    )
    (net (code "163") (name "unconnected-(SV1-Pad2)") (class "Default")
      (node (ref "SV1") (pin "2") (pinfunction "2_2") (pintype "passive"))
    )
    (net (code "164") (name "unconnected-(SV1-Pad4)") (class "Default")
      (node (ref "SV1") (pin "4") (pinfunction "4_4") (pintype "passive"))
    )
    (net (code "165") (name "unconnected-(SV2-Pad2)") (class "Default")
      (node (ref "SV2") (pin "2") (pinfunction "2_2") (pintype "passive"))
    )
    (net (code "166") (name "unconnected-(SV2-Pad4)") (class "Default")
      (node (ref "SV2") (pin "4") (pinfunction "4_4") (pintype "passive"))
    )
    (net (code "167") (name "unconnected-(SV4-Pad2)") (class "Default")
      (node (ref "SV4") (pin "2") (pinfunction "2_2") (pintype "passive"))
    )
    (net (code "168") (name "unconnected-(SV4-Pad4)") (class "Default")
      (node (ref "SV4") (pin "4") (pinfunction "4_4") (pintype "passive"))
    )
    (net (code "169") (name "unconnected-(SV5-Pad2)") (class "Default")
      (node (ref "SV5") (pin "2") (pinfunction "2_2") (pintype "passive"))
    )
    (net (code "170") (name "unconnected-(SV5-Pad4)") (class "Default")
      (node (ref "SV5") (pin "4") (pinfunction "4_4") (pintype "passive"))
    )
    (net (code "171") (name "unconnected-(SV7-Pad2)") (class "Default")
      (node (ref "SV7") (pin "2") (pinfunction "2_2") (pintype "passive"))
    )
    (net (code "172") (name "unconnected-(SV7-Pad4)") (class "Default")
      (node (ref "SV7") (pin "4") (pinfunction "4_4") (pintype "passive"))
    )
    (net (code "173") (name "unconnected-(SV8-Pad2)") (class "Default")
      (node (ref "SV8") (pin "2") (pinfunction "2_2") (pintype "passive"))
    )
    (net (code "174") (name "unconnected-(SV8-Pad4)") (class "Default")
      (node (ref "SV8") (pin "4") (pinfunction "4_4") (pintype "passive"))
    )
    (net (code "175") (name "unconnected-(X1-Pad1)") (class "Default")
      (node (ref "X1") (pin "1") (pinfunction "1_1") (pintype "passive"))
    )
    (net (code "176") (name "unconnected-(X1-Pad4)") (class "Default")
      (node (ref "X1") (pin "4") (pinfunction "4_4") (pintype "passive"))
    )
    (net (code "177") (name "unconnected-(X1-Pad6)") (class "Default")
      (node (ref "X1") (pin "6") (pinfunction "6_6") (pintype "passive"))
    )
    (net (code "178") (name "unconnected-(X1-Pad7)") (class "Default")
      (node (ref "X1") (pin "7") (pinfunction "7_7") (pintype "passive"))
    )
    (net (code "179") (name "unconnected-(X1-Pad9)") (class "Default")
      (node (ref "X1") (pin "9") (pinfunction "9_9") (pintype "passive"))
    )
    (net (code "180") (name "unconnected-(XESS-BSY-Pad17)") (class "Default")
      (node (ref "XESS") (pin "17") (pinfunction "BSY_17") (pintype "bidirectional"))
    )
    (net (code "181") (name "unconnected-(XESS-CLKB-Pad11)") (class "Default")
      (node (ref "XESS") (pin "11") (pinfunction "CLKB_11") (pintype "bidirectional"))
    )
    (net (code "182") (name "unconnected-(XESS-CLKC-Pad64)") (class "Default")
      (node (ref "XESS") (pin "64") (pinfunction "CLKC_64") (pintype "bidirectional"))
    )
    (net (code "183") (name "unconnected-(XESS-CS#-Pad15)") (class "Default")
      (node (ref "XESS") (pin "15") (pinfunction "CS#_15") (pintype "bidirectional"))
    )
    (net (code "184") (name "unconnected-(XESS-D1-Pad25)") (class "Default")
      (node (ref "XESS") (pin "25") (pinfunction "D1_25") (pintype "bidirectional"))
    )
    (net (code "185") (name "unconnected-(XESS-D2-Pad24)") (class "Default")
      (node (ref "XESS") (pin "24") (pinfunction "D2_24") (pintype "bidirectional"))
    )
    (net (code "186") (name "unconnected-(XESS-D15-Pad21)") (class "Default")
      (node (ref "XESS") (pin "21") (pinfunction "D15_21") (pintype "bidirectional"))
    )
    (net (code "187") (name "unconnected-(XESS-E14-Pad20)") (class "Default")
      (node (ref "XESS") (pin "20") (pinfunction "E14_20") (pintype "bidirectional"))
    )
    (net (code "188") (name "unconnected-(XESS-E16-Pad14)") (class "Default")
      (node (ref "XESS") (pin "14") (pinfunction "E16_14") (pintype "bidirectional"))
    )
    (net (code "189") (name "unconnected-(XESS-F5-Pad23)") (class "Default")
      (node (ref "XESS") (pin "23") (pinfunction "F5_23") (pintype "bidirectional"))
    )
    (net (code "190") (name "unconnected-(XESS-F14-Pad13)") (class "Default")
      (node (ref "XESS") (pin "13") (pinfunction "F14_13") (pintype "bidirectional"))
    )
    (net (code "191") (name "unconnected-(XESS-G12-Pad12)") (class "Default")
      (node (ref "XESS") (pin "12") (pinfunction "G12_12") (pintype "bidirectional"))
    )
    (net (code "192") (name "unconnected-(XESS-G13-Pad9)") (class "Default")
      (node (ref "XESS") (pin "9") (pinfunction "G13_9") (pintype "bidirectional"))
    )
    (net (code "193") (name "unconnected-(XESS-G14-Pad8)") (class "Default")
      (node (ref "XESS") (pin "8") (pinfunction "G14_8") (pintype "bidirectional"))
    )
    (net (code "194") (name "unconnected-(XESS-G15-Pad7)") (class "Default")
      (node (ref "XESS") (pin "7") (pinfunction "G15_7") (pintype "bidirectional"))
    )
    (net (code "195") (name "unconnected-(XESS-G16-Pad6)") (class "Default")
      (node (ref "XESS") (pin "6") (pinfunction "G16_6") (pintype "bidirectional"))
    )
    (net (code "196") (name "unconnected-(XESS-H13-Pad5)") (class "Default")
      (node (ref "XESS") (pin "5") (pinfunction "H13_5") (pintype "bidirectional"))
    )
    (net (code "197") (name "unconnected-(XESS-H14-Pad4)") (class "Default")
      (node (ref "XESS") (pin "4") (pinfunction "H14_4") (pintype "bidirectional"))
    )
    (net (code "198") (name "unconnected-(XESS-H15-Pad3)") (class "Default")
      (node (ref "XESS") (pin "3") (pinfunction "H15_3") (pintype "bidirectional"))
    )
    (net (code "199") (name "unconnected-(XESS-H16-Pad1)") (class "Default")
      (node (ref "XESS") (pin "1") (pinfunction "H16_1") (pintype "bidirectional"))
    )
    (net (code "200") (name "unconnected-(XESS-J3-Pad42)") (class "Default")
      (node (ref "XESS") (pin "42") (pinfunction "J3_42") (pintype "bidirectional"))
    )
    (net (code "201") (name "unconnected-(XESS-J13-Pad82)") (class "Default")
      (node (ref "XESS") (pin "82") (pinfunction "J13_82") (pintype "bidirectional"))
    )
    (net (code "202") (name "unconnected-(XESS-J14-Pad83)") (class "Default")
      (node (ref "XESS") (pin "83") (pinfunction "J14_83") (pintype "bidirectional"))
    )
    (net (code "203") (name "unconnected-(XESS-J16-Pad84)") (class "Default")
      (node (ref "XESS") (pin "84") (pinfunction "J16_84") (pintype "bidirectional"))
    )
    (net (code "204") (name "unconnected-(XESS-K1-Pad43)") (class "Default")
      (node (ref "XESS") (pin "43") (pinfunction "K1_43") (pintype "bidirectional"))
    )
    (net (code "205") (name "unconnected-(XESS-K5-Pad45)") (class "Default")
      (node (ref "XESS") (pin "45") (pinfunction "K5_45") (pintype "bidirectional"))
    )
    (net (code "206") (name "unconnected-(XESS-L2-Pad44)") (class "Default")
      (node (ref "XESS") (pin "44") (pinfunction "L2_44") (pintype "bidirectional"))
    )
    (net (code "207") (name "unconnected-(XESS-L3-Pad46)") (class "Default")
      (node (ref "XESS") (pin "46") (pinfunction "L3_46") (pintype "bidirectional"))
    )
    (net (code "208") (name "unconnected-(XESS-L4-Pad49)") (class "Default")
      (node (ref "XESS") (pin "49") (pinfunction "L4_49") (pintype "bidirectional"))
    )
    (net (code "209") (name "unconnected-(XESS-L15-Pad79)") (class "Default")
      (node (ref "XESS") (pin "79") (pinfunction "L15_79") (pintype "bidirectional"))
    )
    (net (code "210") (name "unconnected-(XESS-M1-Pad47)") (class "Default")
      (node (ref "XESS") (pin "47") (pinfunction "M1_47") (pintype "bidirectional"))
    )
    (net (code "211") (name "unconnected-(XESS-M2-Pad48)") (class "Default")
      (node (ref "XESS") (pin "48") (pinfunction "M2_48") (pintype "bidirectional"))
    )
    (net (code "212") (name "unconnected-(XESS-M4-Pad59)") (class "Default")
      (node (ref "XESS") (pin "59") (pinfunction "M4_59") (pintype "bidirectional"))
    )
    (net (code "213") (name "unconnected-(XESS-M10-Pad66)") (class "Default")
      (node (ref "XESS") (pin "66") (pinfunction "M10_66") (pintype "bidirectional"))
    )
    (net (code "214") (name "unconnected-(XESS-M15-Pad78)") (class "Default")
      (node (ref "XESS") (pin "78") (pinfunction "M15_78") (pintype "bidirectional"))
    )
    (net (code "215") (name "unconnected-(XESS-N3-Pad60)") (class "Default")
      (node (ref "XESS") (pin "60") (pinfunction "N3_60") (pintype "bidirectional"))
    )
    (net (code "216") (name "unconnected-(XESS-N15-Pad77)") (class "Default")
      (node (ref "XESS") (pin "77") (pinfunction "N15_77") (pintype "bidirectional"))
    )
    (net (code "217") (name "unconnected-(XESS-P$53-Pad53)") (class "Default")
      (node (ref "XESS") (pin "53") (pinfunction "P$53_53") (pintype "bidirectional"))
    )
    (net (code "218") (name "unconnected-(XESS-P$63-Pad63)") (class "Default")
      (node (ref "XESS") (pin "63") (pinfunction "P$63_63") (pintype "bidirectional"))
    )
    (net (code "219") (name "unconnected-(XESS-P$65-Pad65)") (class "Default")
      (node (ref "XESS") (pin "65") (pinfunction "P$65_65") (pintype "bidirectional"))
    )
    (net (code "220") (name "unconnected-(XESS-P$72-Pad72)") (class "Default")
      (node (ref "XESS") (pin "72") (pinfunction "P$72_72") (pintype "bidirectional"))
    )
    (net (code "221") (name "unconnected-(XESS-P$73-Pad73)") (class "Default")
      (node (ref "XESS") (pin "73") (pinfunction "P$73_73") (pintype "bidirectional"))
    )
    (net (code "222") (name "unconnected-(XESS-P$74-Pad74)") (class "Default")
      (node (ref "XESS") (pin "74") (pinfunction "P$74_74") (pintype "bidirectional"))
    )
    (net (code "223") (name "unconnected-(XESS-P$75-Pad75)") (class "Default")
      (node (ref "XESS") (pin "75") (pinfunction "P$75_75") (pintype "bidirectional"))
    )
    (net (code "224") (name "unconnected-(XESS-P$76-Pad76)") (class "Default")
      (node (ref "XESS") (pin "76") (pinfunction "P$76_76") (pintype "bidirectional"))
    )
    (net (code "225") (name "unconnected-(XESS-P1-Pad58)") (class "Default")
      (node (ref "XESS") (pin "58") (pinfunction "P1_58") (pintype "bidirectional"))
    )
    (net (code "226") (name "unconnected-(XESS-P2-Pad61)") (class "Default")
      (node (ref "XESS") (pin "61") (pinfunction "P2_61") (pintype "bidirectional"))
    )
    (net (code "227") (name "unconnected-(XESS-P11-Pad67)") (class "Default")
      (node (ref "XESS") (pin "67") (pinfunction "P11_67") (pintype "bidirectional"))
    )
    (net (code "228") (name "unconnected-(XESS-PROG#-Pad55)") (class "Default")
      (node (ref "XESS") (pin "55") (pinfunction "PROG#_55") (pintype "bidirectional"))
    )
    (net (code "229") (name "unconnected-(XESS-R1-Pad62)") (class "Default")
      (node (ref "XESS") (pin "62") (pinfunction "R1_62") (pintype "bidirectional"))
    )
    (net (code "230") (name "unconnected-(XESS-R12-Pad69)") (class "Default")
      (node (ref "XESS") (pin "69") (pinfunction "R12_69") (pintype "bidirectional"))
    )
    (net (code "231") (name "unconnected-(XESS-T12-Pad68)") (class "Default")
      (node (ref "XESS") (pin "68") (pinfunction "T12_68") (pintype "bidirectional"))
    )
    (net (code "232") (name "unconnected-(XESS-TCK-Pad16)") (class "Default")
      (node (ref "XESS") (pin "16") (pinfunction "TCK_16") (pintype "bidirectional"))
    )
    (net (code "233") (name "unconnected-(XESS-WR#-Pad30)") (class "Default")
      (node (ref "XESS") (pin "30") (pinfunction "WR#_30") (pintype "bidirectional"))
    )
  )
)
